# HFT_VHF-UHF-TRX_1V0.net
KiCad netlist of a schematic drawn in EAGLE
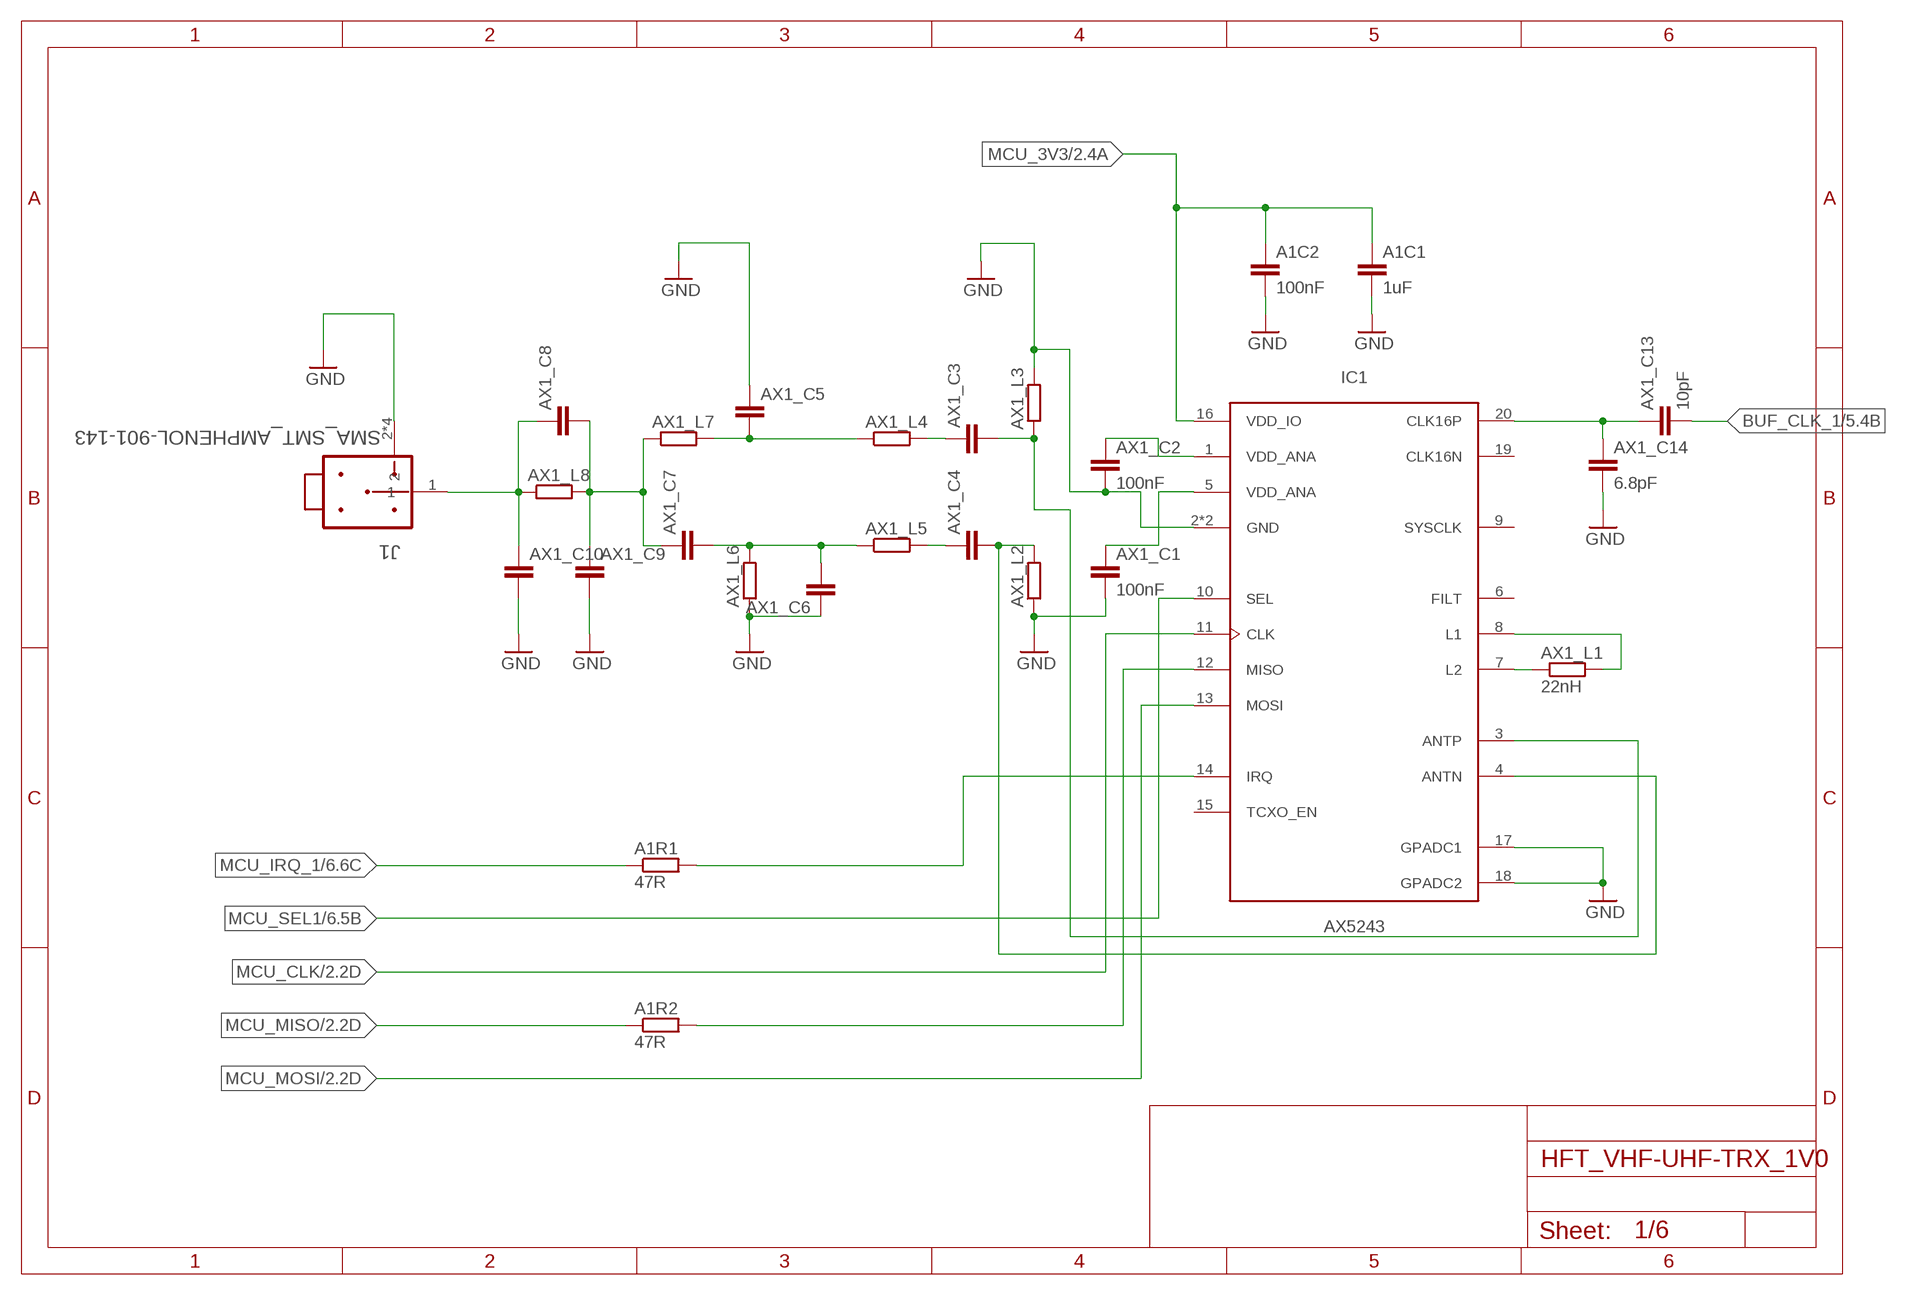
[diagram p0: schematic, sheet 1]
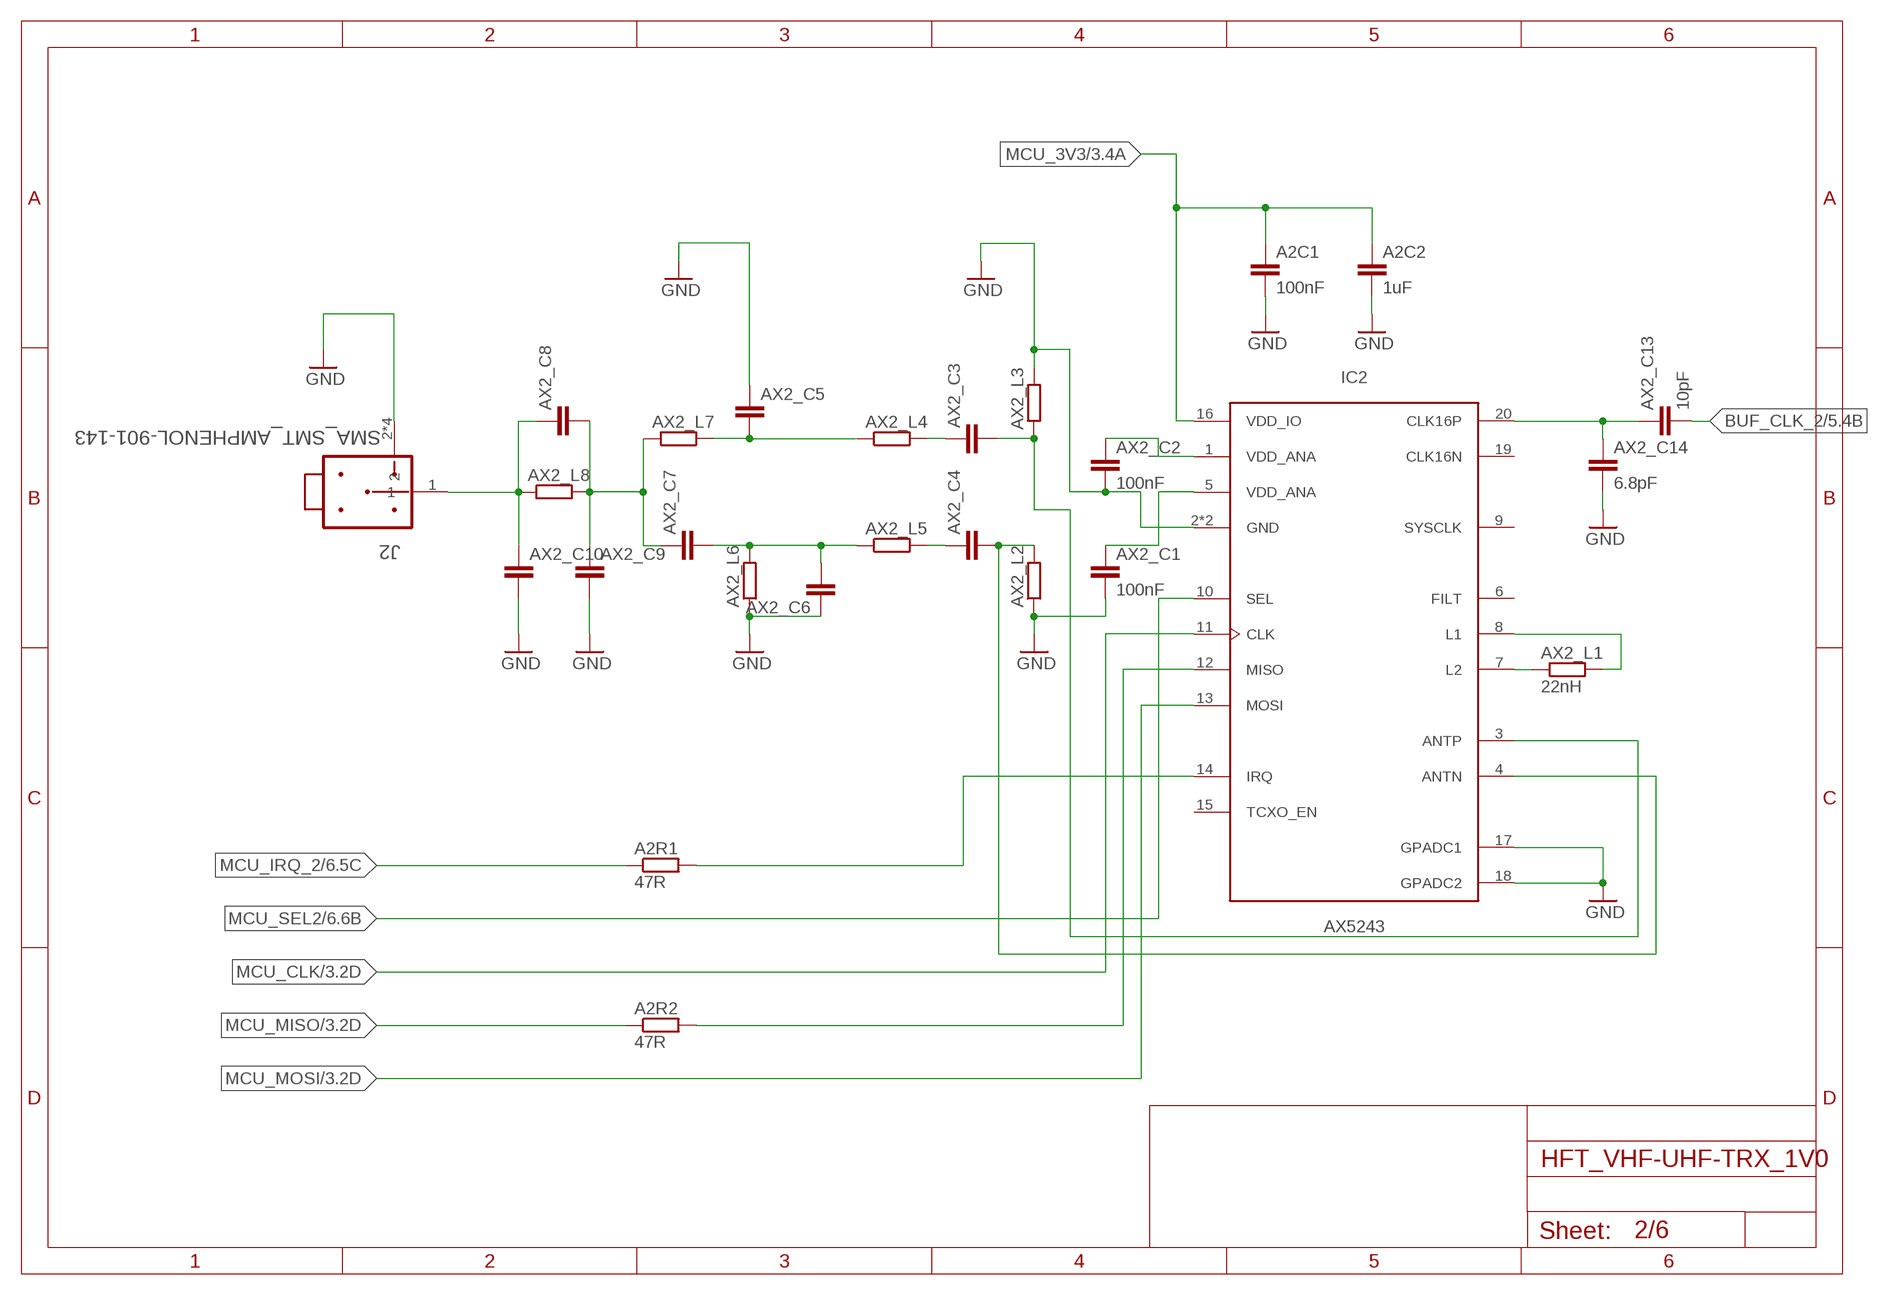
[diagram p1: schematic, sheet 2]
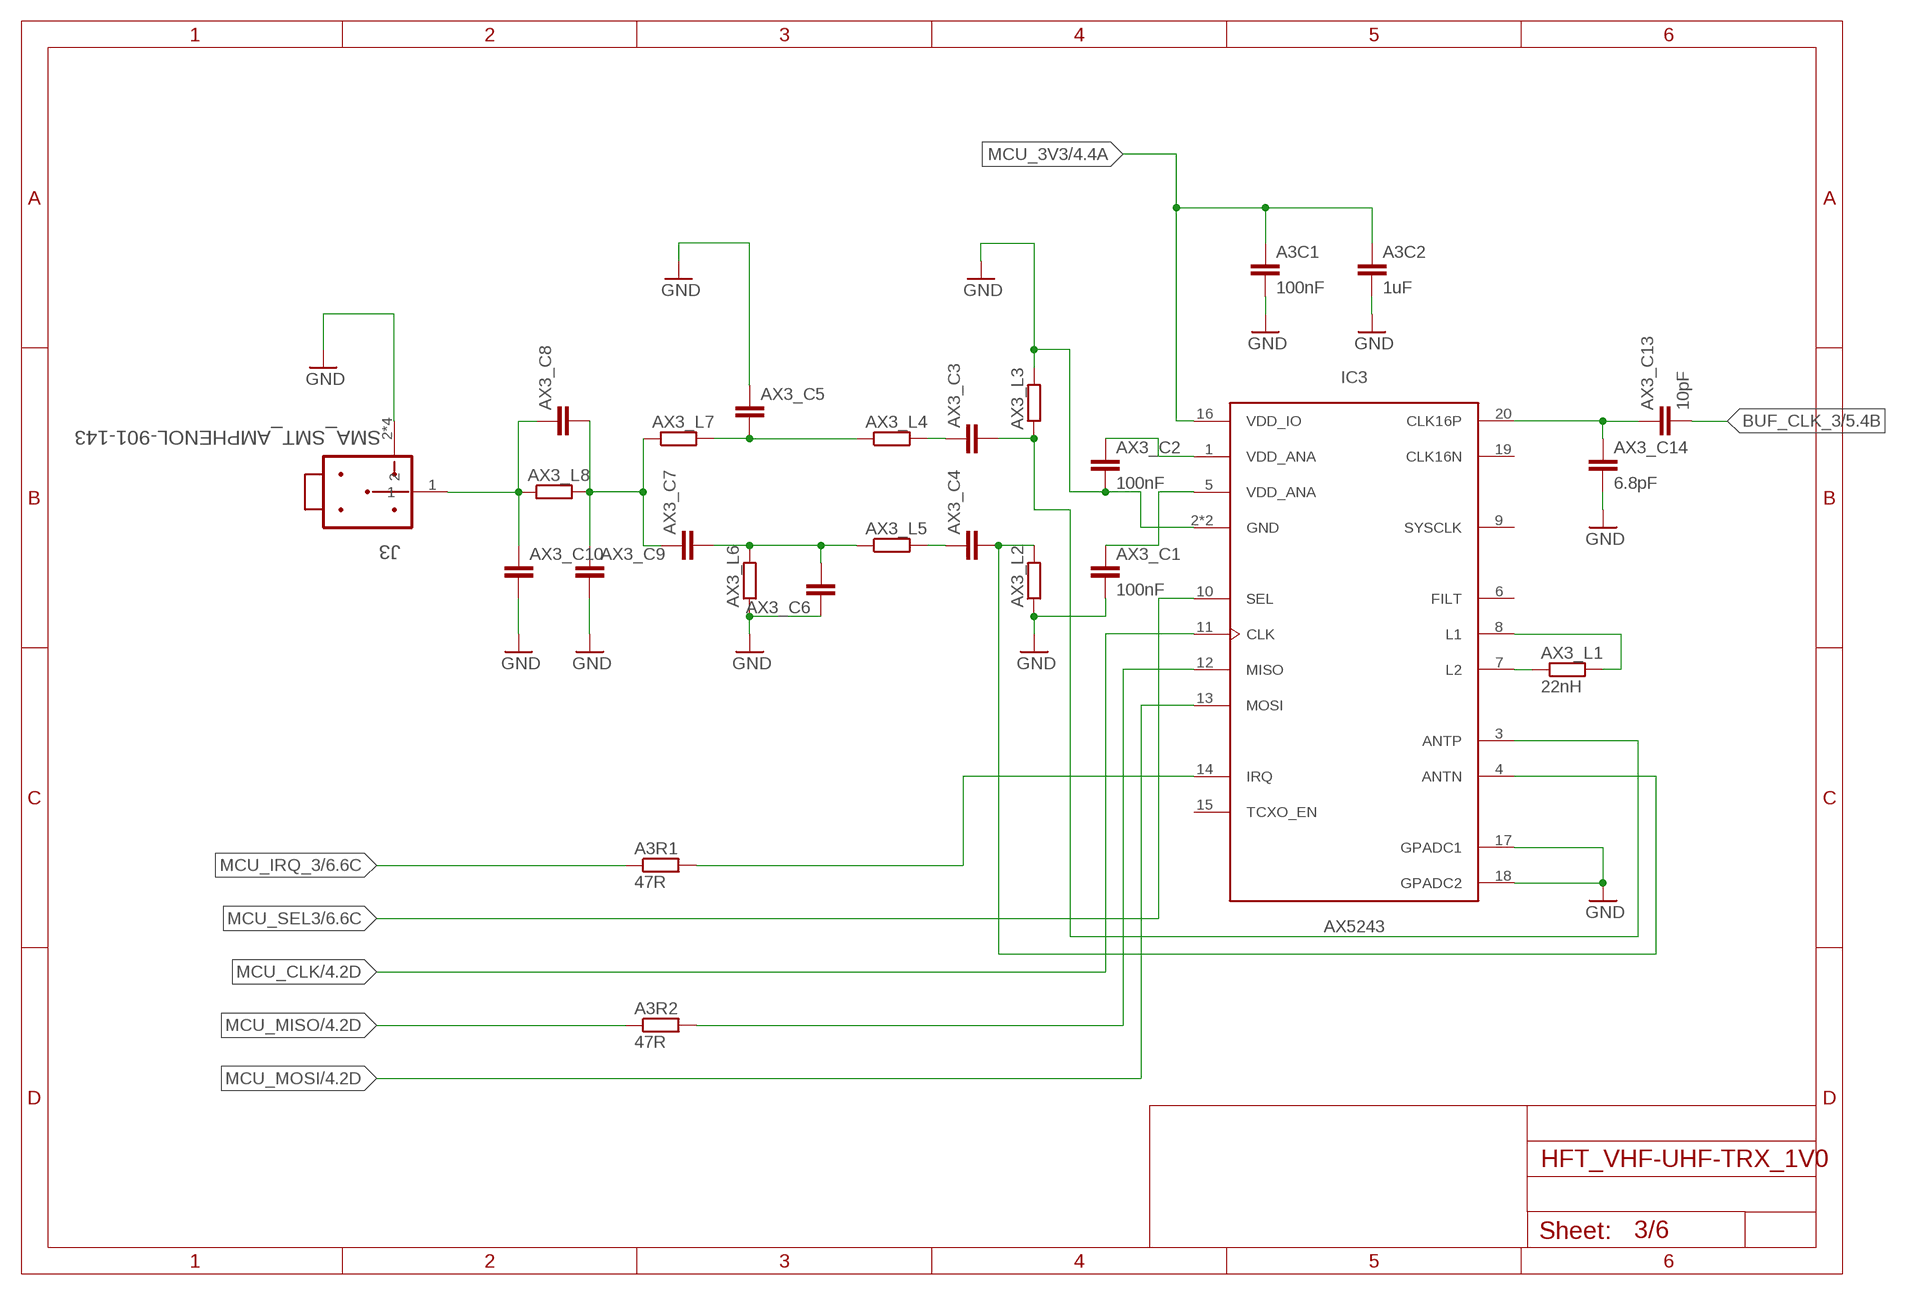
[diagram p2: schematic, sheet 3]
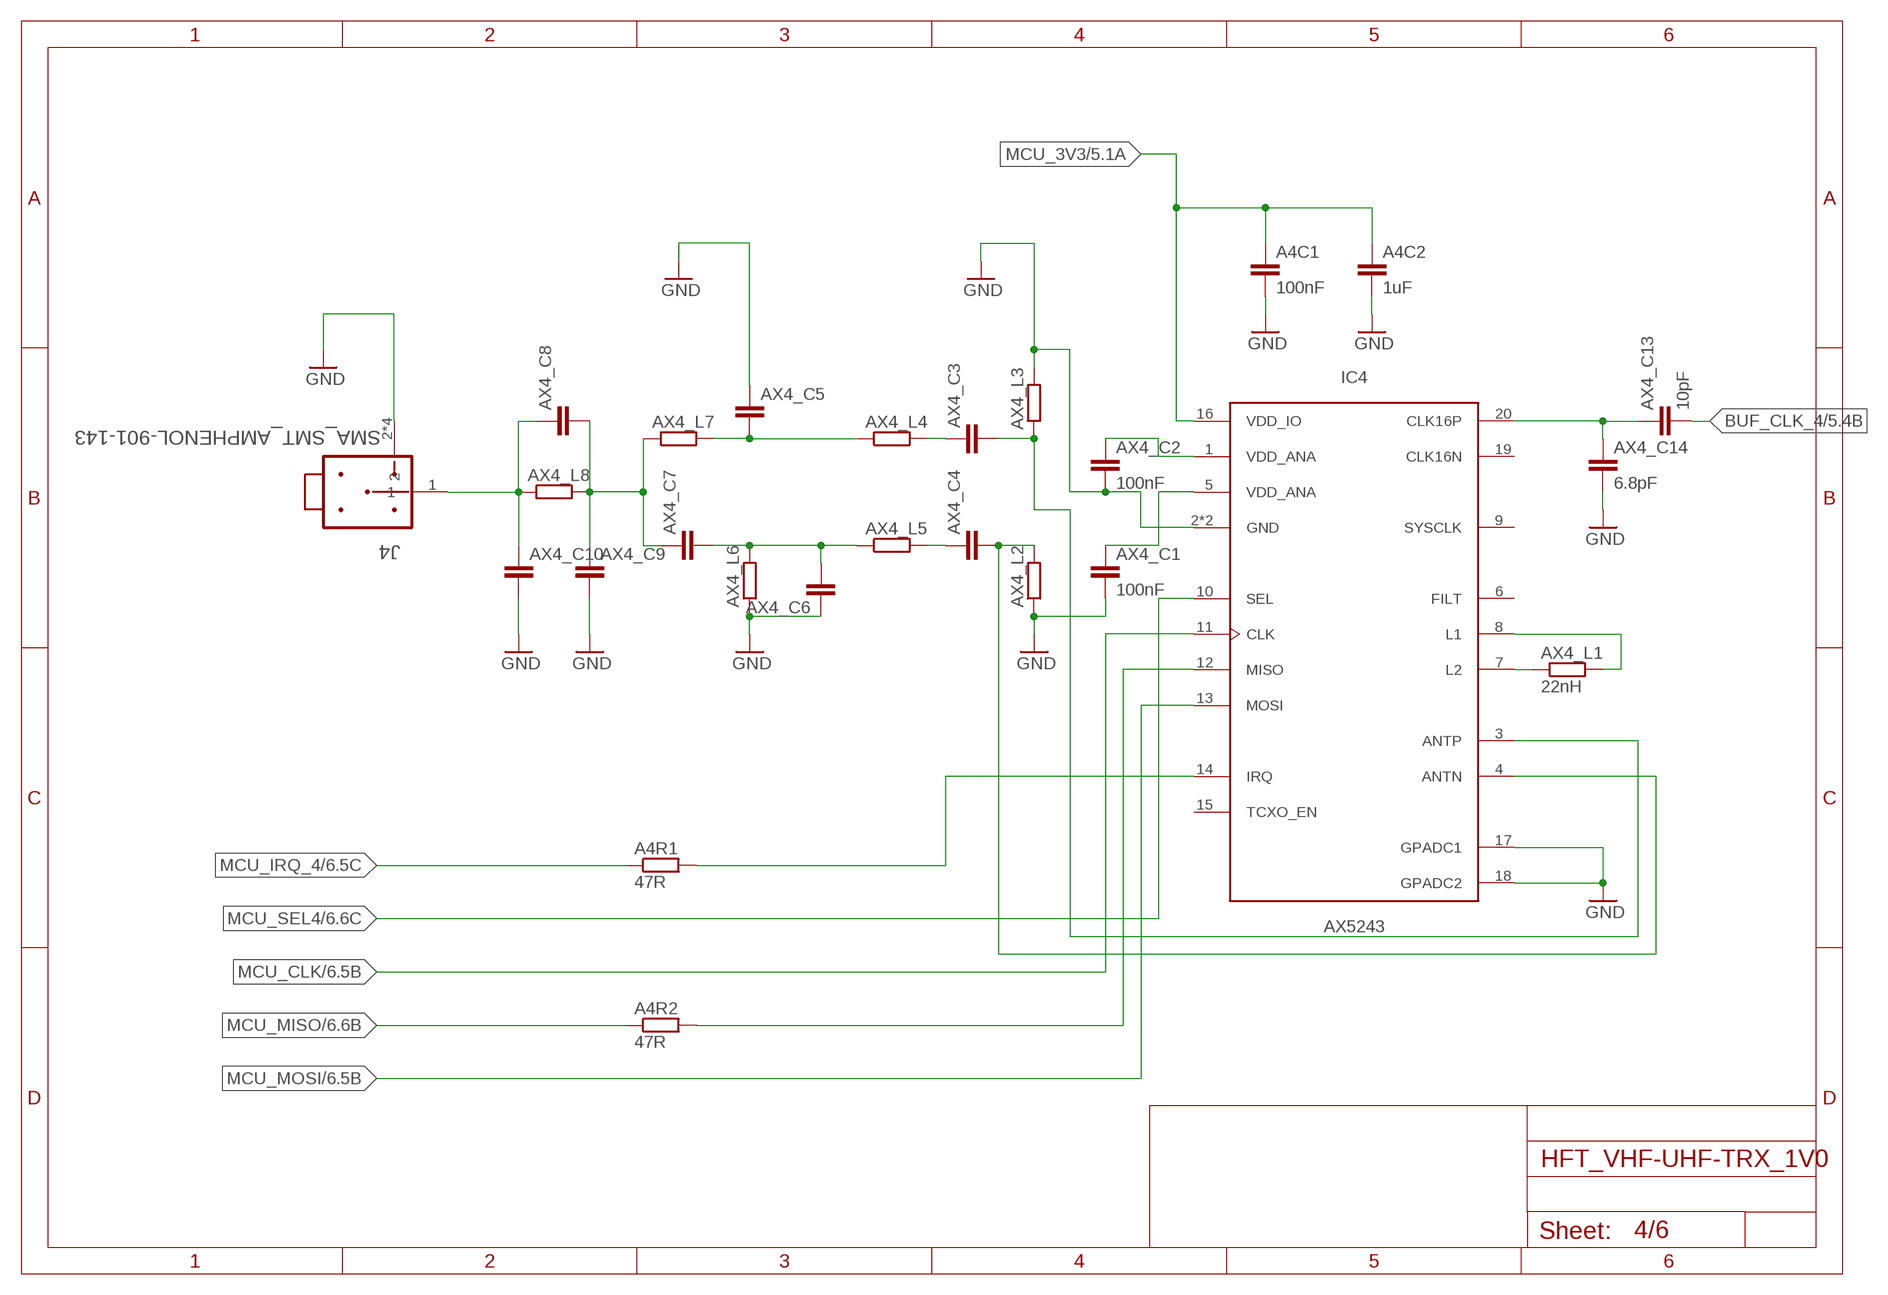
[diagram p3: schematic, sheet 4]
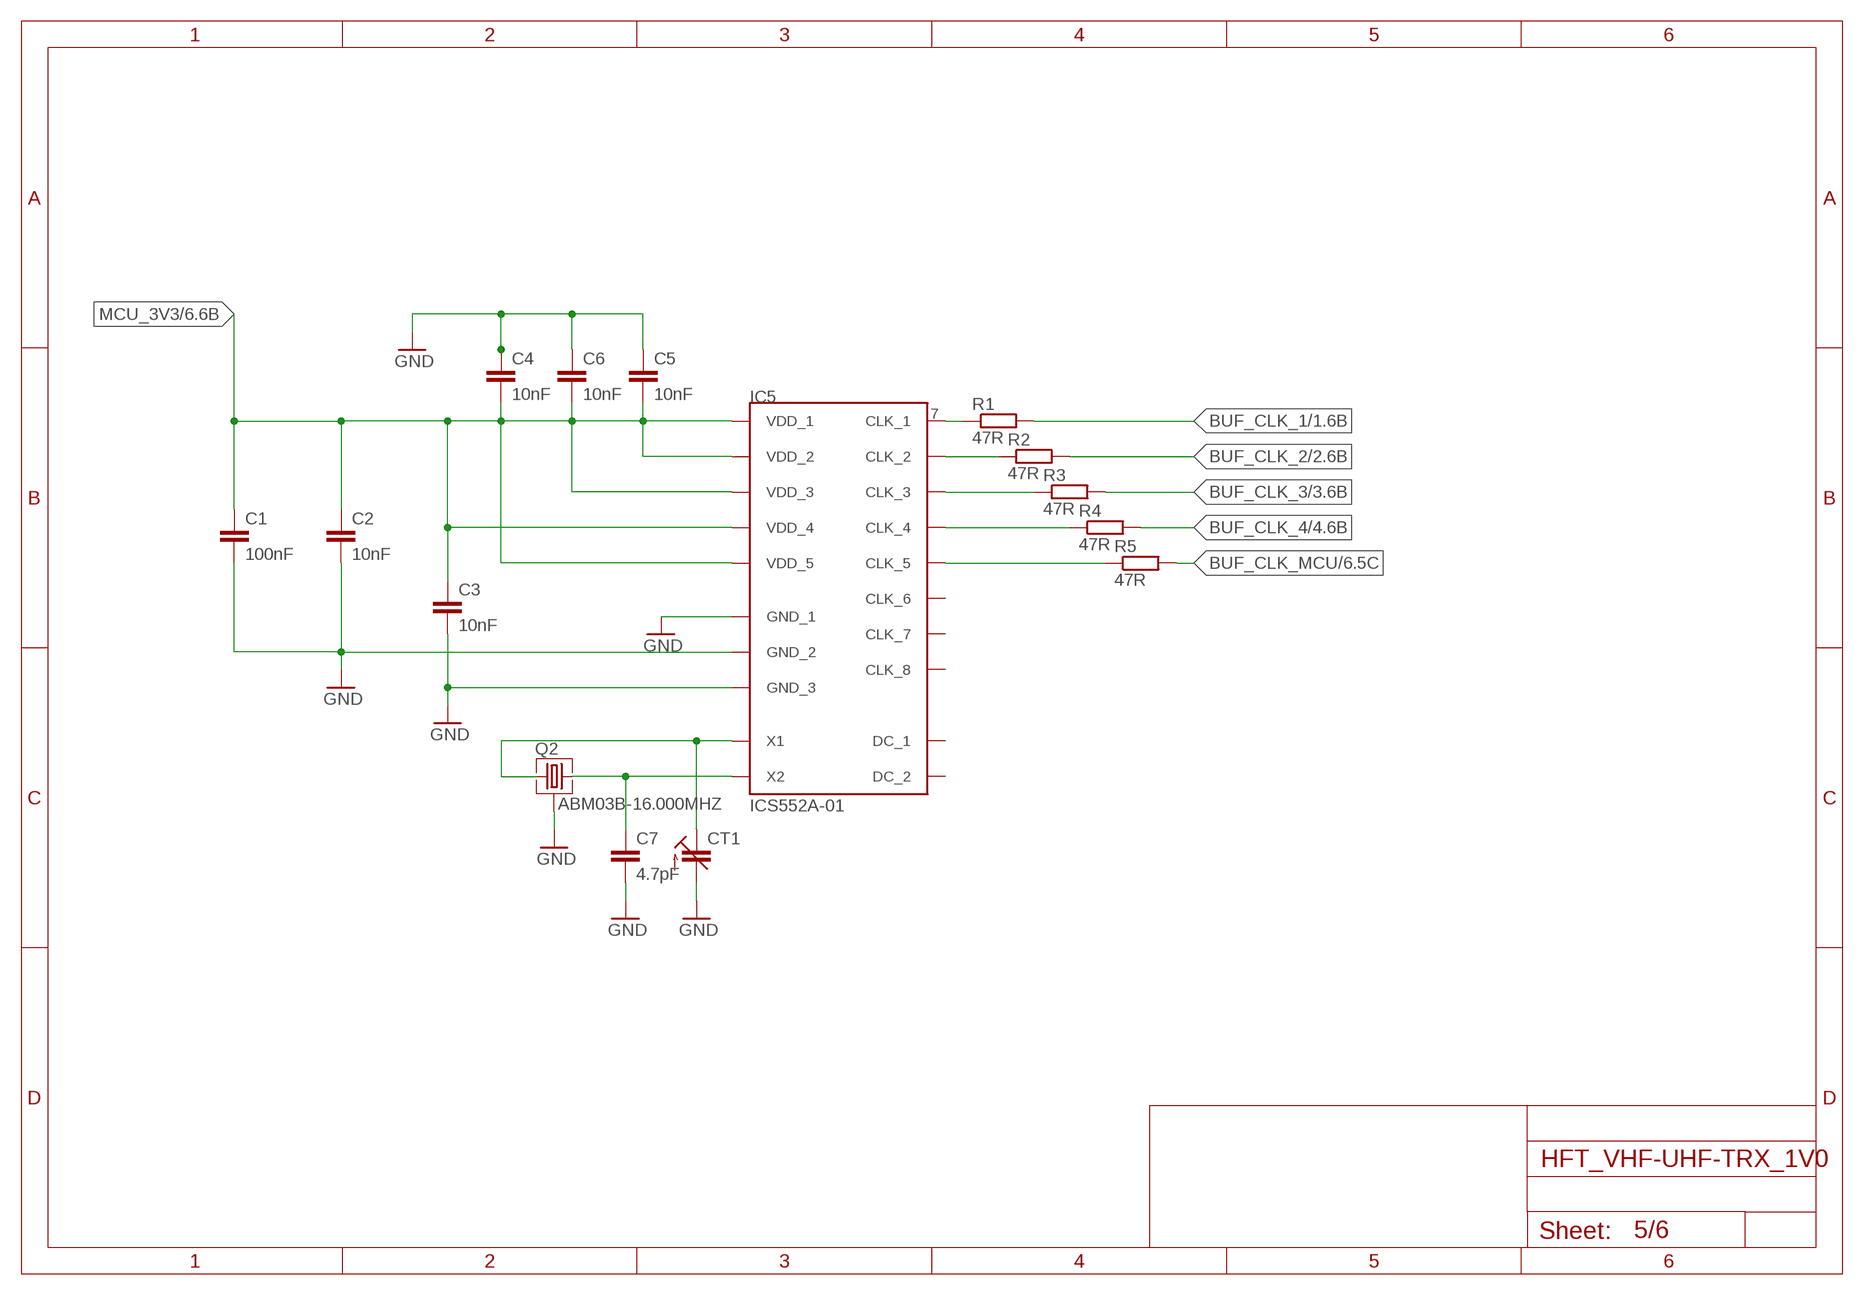
[diagram p4: schematic, sheet 5]
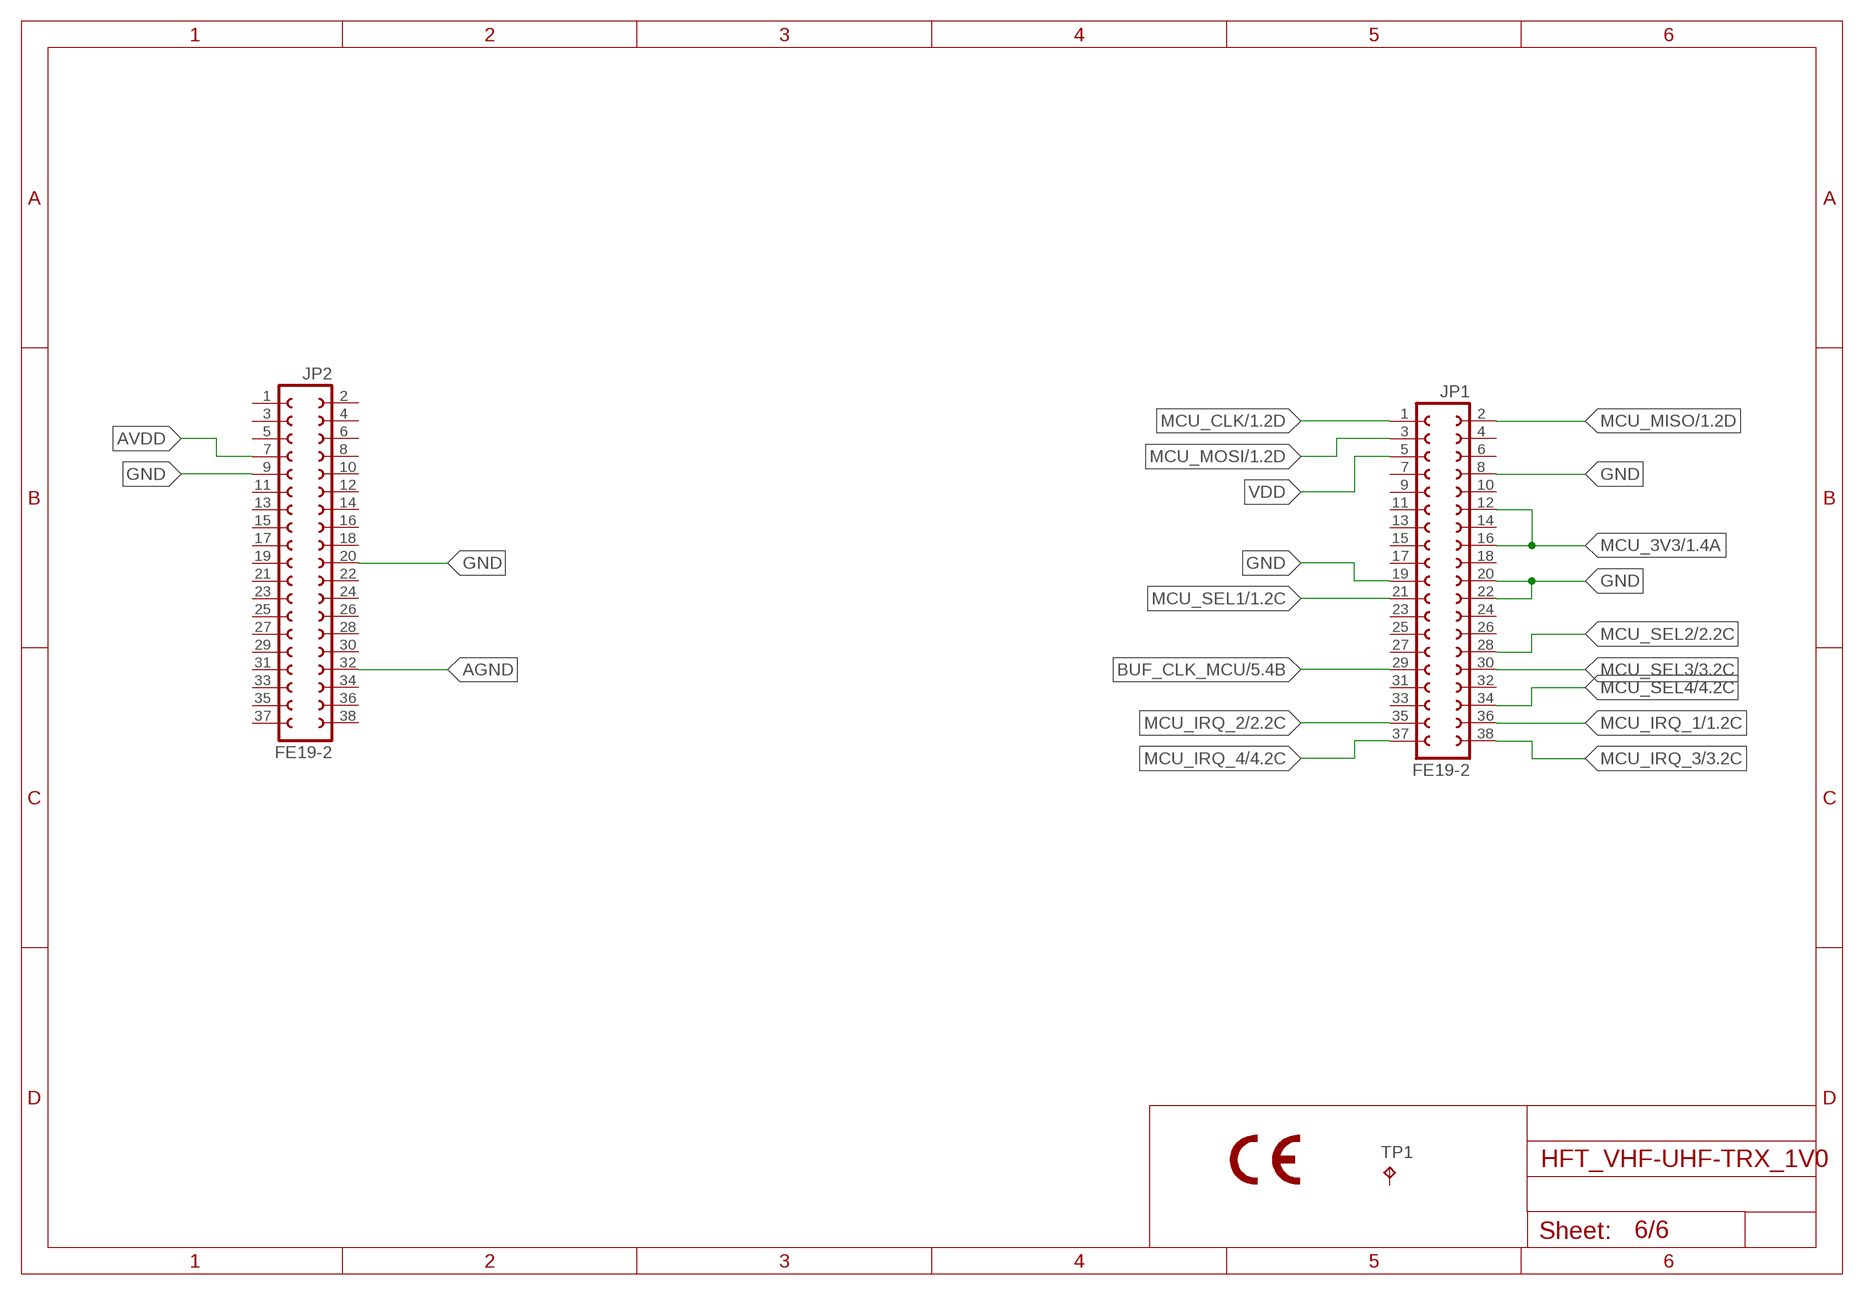
[diagram p5: schematic, sheet 6]

(export (version "E")
  (design (tool "Eeschema 10.0.6"))
  (components
    (comp (ref "JP1")
      (value "FE19-2")
      (footprint "eagle-import:FE19-2")
      (libsource (lib "eagle-import") (part "FE19-2"))
    )
    (comp (ref "JP2")
      (value "FE19-2")
      (footprint "eagle-import:FE19-2")
      (libsource (lib "eagle-import") (part "FE19-2"))
    )
    (comp (ref "TP1")
      (value "TPB1,27")
      (footprint "eagle-import:B1,27")
      (libsource (lib "eagle-import") (part "TPB1,27"))
    )
    (comp (ref "C1")
      (value "100nF")
      (footprint "eagle-import:C0805")
      (libsource (lib "eagle-import") (part "C-EUC0805"))
    )
    (comp (ref "C2")
      (value "10nF")
      (footprint "eagle-import:C0805")
      (libsource (lib "eagle-import") (part "C-EUC0805"))
    )
    (comp (ref "C3")
      (value "10nF")
      (footprint "eagle-import:C0805")
      (libsource (lib "eagle-import") (part "C-EUC0805"))
    )
    (comp (ref "C4")
      (value "10nF")
      (footprint "eagle-import:C0805")
      (libsource (lib "eagle-import") (part "C-EUC0805"))
    )
    (comp (ref "C5")
      (value "10nF")
      (footprint "eagle-import:C0805")
      (libsource (lib "eagle-import") (part "C-EUC0805"))
    )
    (comp (ref "C6")
      (value "10nF")
      (footprint "eagle-import:C0805")
      (libsource (lib "eagle-import") (part "C-EUC0805"))
    )
    (comp (ref "C7")
      (value "4.7pF")
      (footprint "eagle-import:C0805")
      (libsource (lib "eagle-import") (part "C-EUC0805"))
    )
    (comp (ref "CT1")
      (value "C-TRIMM3MM2_2MM5")
      (footprint "eagle-import:3MM2_X_2MM5")
      (libsource (lib "eagle-import") (part "C-TRIMM3MM2_2MM5"))
    )
    (comp (ref "IC5")
      (value "ICS552A-01")
      (footprint "eagle-import:SSOP20")
      (libsource (lib "eagle-import") (part "ICS552A-01"))
    )
    (comp (ref "Q2")
      (value "ABM03B-16.000MHZ")
      (footprint "eagle-import:ABM03B")
      (libsource (lib "eagle-import") (part "ABM03B-16.000MHZ"))
    )
    (comp (ref "R1")
      (value "47R")
      (footprint "eagle-import:R0805")
      (libsource (lib "eagle-import") (part "R-EU_R0805"))
    )
    (comp (ref "R2")
      (value "47R")
      (footprint "eagle-import:R0805")
      (libsource (lib "eagle-import") (part "R-EU_R0805"))
    )
    (comp (ref "R3")
      (value "47R")
      (footprint "eagle-import:R0805")
      (libsource (lib "eagle-import") (part "R-EU_R0805"))
    )
    (comp (ref "R4")
      (value "47R")
      (footprint "eagle-import:R0805")
      (libsource (lib "eagle-import") (part "R-EU_R0805"))
    )
    (comp (ref "R5")
      (value "47R")
      (footprint "eagle-import:R0805")
      (libsource (lib "eagle-import") (part "R-EU_R0805"))
    )
    (comp (ref "A3C1")
      (value "100nF")
      (footprint "eagle-import:C0805")
      (libsource (lib "eagle-import") (part "C-EUC0805"))
    )
    (comp (ref "A3C2")
      (value "1uF")
      (footprint "eagle-import:C0805")
      (libsource (lib "eagle-import") (part "C-EUC0805"))
    )
    (comp (ref "A3R1")
      (value "47R")
      (footprint "eagle-import:R0805")
      (libsource (lib "eagle-import") (part "R-EU_R0805"))
    )
    (comp (ref "A3R2")
      (value "47R")
      (footprint "eagle-import:R0805")
      (libsource (lib "eagle-import") (part "R-EU_R0805"))
    )
    (comp (ref "AX3_C1")
      (value "100nF")
      (footprint "eagle-import:C0805")
      (libsource (lib "eagle-import") (part "C-EUC0805"))
    )
    (comp (ref "AX3_C2")
      (value "100nF")
      (footprint "eagle-import:C0805")
      (libsource (lib "eagle-import") (part "C-EUC0805"))
    )
    (comp (ref "AX3_C3")
      (value "C-EUC0805")
      (footprint "eagle-import:C0805")
      (libsource (lib "eagle-import") (part "C-EUC0805"))
    )
    (comp (ref "AX3_C4")
      (value "C-EUC0805")
      (footprint "eagle-import:C0805")
      (libsource (lib "eagle-import") (part "C-EUC0805"))
    )
    (comp (ref "AX3_C5")
      (value "C-EUC0805")
      (footprint "eagle-import:C0805")
      (libsource (lib "eagle-import") (part "C-EUC0805"))
    )
    (comp (ref "AX3_C6")
      (value "C-EUC0805")
      (footprint "eagle-import:C0805")
      (libsource (lib "eagle-import") (part "C-EUC0805"))
    )
    (comp (ref "AX3_C7")
      (value "C-EUC0805")
      (footprint "eagle-import:C0805")
      (libsource (lib "eagle-import") (part "C-EUC0805"))
    )
    (comp (ref "AX3_C8")
      (value "C-EUC0805")
      (footprint "eagle-import:C0805")
      (libsource (lib "eagle-import") (part "C-EUC0805"))
    )
    (comp (ref "AX3_C9")
      (value "C-EUC0805")
      (footprint "eagle-import:C0805")
      (libsource (lib "eagle-import") (part "C-EUC0805"))
    )
    (comp (ref "AX3_C10")
      (value "C-EUC0805")
      (footprint "eagle-import:C0805")
      (libsource (lib "eagle-import") (part "C-EUC0805"))
    )
    (comp (ref "AX3_C13")
      (value "10pF")
      (footprint "eagle-import:C0805")
      (libsource (lib "eagle-import") (part "C-EUC0805"))
    )
    (comp (ref "AX3_C14")
      (value "6.8pF")
      (footprint "eagle-import:C0805")
      (libsource (lib "eagle-import") (part "C-EUC0805"))
    )
    (comp (ref "AX3_L1")
      (value "22nH")
      (footprint "eagle-import:R0805")
      (libsource (lib "eagle-import") (part "R-EU_R0805"))
    )
    (comp (ref "AX3_L2")
      (value "R-EU_R0805")
      (footprint "eagle-import:R0805")
      (libsource (lib "eagle-import") (part "R-EU_R0805"))
    )
    (comp (ref "AX3_L3")
      (value "R-EU_R0805")
      (footprint "eagle-import:R0805")
      (libsource (lib "eagle-import") (part "R-EU_R0805"))
    )
    (comp (ref "AX3_L4")
      (value "R-EU_R0805")
      (footprint "eagle-import:R0805")
      (libsource (lib "eagle-import") (part "R-EU_R0805"))
    )
    (comp (ref "AX3_L5")
      (value "R-EU_R0805")
      (footprint "eagle-import:R0805")
      (libsource (lib "eagle-import") (part "R-EU_R0805"))
    )
    (comp (ref "AX3_L6")
      (value "R-EU_R0805")
      (footprint "eagle-import:R0805")
      (libsource (lib "eagle-import") (part "R-EU_R0805"))
    )
    (comp (ref "AX3_L7")
      (value "R-EU_R0805")
      (footprint "eagle-import:R0805")
      (libsource (lib "eagle-import") (part "R-EU_R0805"))
    )
    (comp (ref "AX3_L8")
      (value "R-EU_R0805")
      (footprint "eagle-import:R0805")
      (libsource (lib "eagle-import") (part "R-EU_R0805"))
    )
    (comp (ref "IC3")
      (value "AX5243")
      (footprint "eagle-import:QFN20-4X4-0P5-PAD")
      (libsource (lib "eagle-import") (part "AX5243"))
    )
    (comp (ref "J3")
      (value "SMA_SMT_AMPHENOL-901-143")
      (footprint "eagle-import:SMA_SMT_AMPHENOL_901-143")
      (fields (field (name "MPN") "901-143"))
      (libsource (lib "eagle-import") (part "SMA_SMT_AMPHENOL-901-143"))
    )
    (comp (ref "A2C1")
      (value "100nF")
      (footprint "eagle-import:C0805")
      (libsource (lib "eagle-import") (part "C-EUC0805"))
    )
    (comp (ref "A2C2")
      (value "1uF")
      (footprint "eagle-import:C0805")
      (libsource (lib "eagle-import") (part "C-EUC0805"))
    )
    (comp (ref "A2R1")
      (value "47R")
      (footprint "eagle-import:R0805")
      (libsource (lib "eagle-import") (part "R-EU_R0805"))
    )
    (comp (ref "A2R2")
      (value "47R")
      (footprint "eagle-import:R0805")
      (libsource (lib "eagle-import") (part "R-EU_R0805"))
    )
    (comp (ref "AX2_C1")
      (value "100nF")
      (footprint "eagle-import:C0805")
      (libsource (lib "eagle-import") (part "C-EUC0805"))
    )
    (comp (ref "AX2_C2")
      (value "100nF")
      (footprint "eagle-import:C0805")
      (libsource (lib "eagle-import") (part "C-EUC0805"))
    )
    (comp (ref "AX2_C3")
      (value "C-EUC0805")
      (footprint "eagle-import:C0805")
      (libsource (lib "eagle-import") (part "C-EUC0805"))
    )
    (comp (ref "AX2_C4")
      (value "C-EUC0805")
      (footprint "eagle-import:C0805")
      (libsource (lib "eagle-import") (part "C-EUC0805"))
    )
    (comp (ref "AX2_C5")
      (value "C-EUC0805")
      (footprint "eagle-import:C0805")
      (libsource (lib "eagle-import") (part "C-EUC0805"))
    )
    (comp (ref "AX2_C6")
      (value "C-EUC0805")
      (footprint "eagle-import:C0805")
      (libsource (lib "eagle-import") (part "C-EUC0805"))
    )
    (comp (ref "AX2_C7")
      (value "C-EUC0805")
      (footprint "eagle-import:C0805")
      (libsource (lib "eagle-import") (part "C-EUC0805"))
    )
    (comp (ref "AX2_C8")
      (value "C-EUC0805")
      (footprint "eagle-import:C0805")
      (libsource (lib "eagle-import") (part "C-EUC0805"))
    )
    (comp (ref "AX2_C9")
      (value "C-EUC0805")
      (footprint "eagle-import:C0805")
      (libsource (lib "eagle-import") (part "C-EUC0805"))
    )
    (comp (ref "AX2_C10")
      (value "C-EUC0805")
      (footprint "eagle-import:C0805")
      (libsource (lib "eagle-import") (part "C-EUC0805"))
    )
    (comp (ref "AX2_C13")
      (value "10pF")
      (footprint "eagle-import:C0805")
      (libsource (lib "eagle-import") (part "C-EUC0805"))
    )
    (comp (ref "AX2_C14")
      (value "6.8pF")
      (footprint "eagle-import:C0805")
      (libsource (lib "eagle-import") (part "C-EUC0805"))
    )
    (comp (ref "AX2_L1")
      (value "22nH")
      (footprint "eagle-import:R0805")
      (libsource (lib "eagle-import") (part "R-EU_R0805"))
    )
    (comp (ref "AX2_L2")
      (value "R-EU_R0805")
      (footprint "eagle-import:R0805")
      (libsource (lib "eagle-import") (part "R-EU_R0805"))
    )
    (comp (ref "AX2_L3")
      (value "R-EU_R0805")
      (footprint "eagle-import:R0805")
      (libsource (lib "eagle-import") (part "R-EU_R0805"))
    )
    (comp (ref "AX2_L4")
      (value "R-EU_R0805")
      (footprint "eagle-import:R0805")
      (libsource (lib "eagle-import") (part "R-EU_R0805"))
    )
    (comp (ref "AX2_L5")
      (value "R-EU_R0805")
      (footprint "eagle-import:R0805")
      (libsource (lib "eagle-import") (part "R-EU_R0805"))
    )
    (comp (ref "AX2_L6")
      (value "R-EU_R0805")
      (footprint "eagle-import:R0805")
      (libsource (lib "eagle-import") (part "R-EU_R0805"))
    )
    (comp (ref "AX2_L7")
      (value "R-EU_R0805")
      (footprint "eagle-import:R0805")
      (libsource (lib "eagle-import") (part "R-EU_R0805"))
    )
    (comp (ref "AX2_L8")
      (value "R-EU_R0805")
      (footprint "eagle-import:R0805")
      (libsource (lib "eagle-import") (part "R-EU_R0805"))
    )
    (comp (ref "IC2")
      (value "AX5243")
      (footprint "eagle-import:QFN20-4X4-0P5-PAD")
      (libsource (lib "eagle-import") (part "AX5243"))
    )
    (comp (ref "J2")
      (value "SMA_SMT_AMPHENOL-901-143")
      (footprint "eagle-import:SMA_SMT_AMPHENOL_901-143")
      (fields (field (name "MPN") "901-143"))
      (libsource (lib "eagle-import") (part "SMA_SMT_AMPHENOL-901-143"))
    )
    (comp (ref "A4C1")
      (value "100nF")
      (footprint "eagle-import:C0805")
      (libsource (lib "eagle-import") (part "C-EUC0805"))
    )
    (comp (ref "A4C2")
      (value "1uF")
      (footprint "eagle-import:C0805")
      (libsource (lib "eagle-import") (part "C-EUC0805"))
    )
    (comp (ref "A4R1")
      (value "47R")
      (footprint "eagle-import:R0805")
      (libsource (lib "eagle-import") (part "R-EU_R0805"))
    )
    (comp (ref "A4R2")
      (value "47R")
      (footprint "eagle-import:R0805")
      (libsource (lib "eagle-import") (part "R-EU_R0805"))
    )
    (comp (ref "AX4_C1")
      (value "100nF")
      (footprint "eagle-import:C0805")
      (libsource (lib "eagle-import") (part "C-EUC0805"))
    )
    (comp (ref "AX4_C2")
      (value "100nF")
      (footprint "eagle-import:C0805")
      (libsource (lib "eagle-import") (part "C-EUC0805"))
    )
    (comp (ref "AX4_C3")
      (value "C-EUC0805")
      (footprint "eagle-import:C0805")
      (libsource (lib "eagle-import") (part "C-EUC0805"))
    )
    (comp (ref "AX4_C4")
      (value "C-EUC0805")
      (footprint "eagle-import:C0805")
      (libsource (lib "eagle-import") (part "C-EUC0805"))
    )
    (comp (ref "AX4_C5")
      (value "C-EUC0805")
      (footprint "eagle-import:C0805")
      (libsource (lib "eagle-import") (part "C-EUC0805"))
    )
    (comp (ref "AX4_C6")
      (value "C-EUC0805")
      (footprint "eagle-import:C0805")
      (libsource (lib "eagle-import") (part "C-EUC0805"))
    )
    (comp (ref "AX4_C7")
      (value "C-EUC0805")
      (footprint "eagle-import:C0805")
      (libsource (lib "eagle-import") (part "C-EUC0805"))
    )
    (comp (ref "AX4_C8")
      (value "C-EUC0805")
      (footprint "eagle-import:C0805")
      (libsource (lib "eagle-import") (part "C-EUC0805"))
    )
    (comp (ref "AX4_C9")
      (value "C-EUC0805")
      (footprint "eagle-import:C0805")
      (libsource (lib "eagle-import") (part "C-EUC0805"))
    )
    (comp (ref "AX4_C10")
      (value "C-EUC0805")
      (footprint "eagle-import:C0805")
      (libsource (lib "eagle-import") (part "C-EUC0805"))
    )
    (comp (ref "AX4_C13")
      (value "10pF")
      (footprint "eagle-import:C0805")
      (libsource (lib "eagle-import") (part "C-EUC0805"))
    )
    (comp (ref "AX4_C14")
      (value "6.8pF")
      (footprint "eagle-import:C0805")
      (libsource (lib "eagle-import") (part "C-EUC0805"))
    )
    (comp (ref "AX4_L1")
      (value "22nH")
      (footprint "eagle-import:R0805")
      (libsource (lib "eagle-import") (part "R-EU_R0805"))
    )
    (comp (ref "AX4_L2")
      (value "R-EU_R0805")
      (footprint "eagle-import:R0805")
      (libsource (lib "eagle-import") (part "R-EU_R0805"))
    )
    (comp (ref "AX4_L3")
      (value "R-EU_R0805")
      (footprint "eagle-import:R0805")
      (libsource (lib "eagle-import") (part "R-EU_R0805"))
    )
    (comp (ref "AX4_L4")
      (value "R-EU_R0805")
      (footprint "eagle-import:R0805")
      (libsource (lib "eagle-import") (part "R-EU_R0805"))
    )
    (comp (ref "AX4_L5")
      (value "R-EU_R0805")
      (footprint "eagle-import:R0805")
      (libsource (lib "eagle-import") (part "R-EU_R0805"))
    )
    (comp (ref "AX4_L6")
      (value "R-EU_R0805")
      (footprint "eagle-import:R0805")
      (libsource (lib "eagle-import") (part "R-EU_R0805"))
    )
    (comp (ref "AX4_L7")
      (value "R-EU_R0805")
      (footprint "eagle-import:R0805")
      (libsource (lib "eagle-import") (part "R-EU_R0805"))
    )
    (comp (ref "AX4_L8")
      (value "R-EU_R0805")
      (footprint "eagle-import:R0805")
      (libsource (lib "eagle-import") (part "R-EU_R0805"))
    )
    (comp (ref "IC4")
      (value "AX5243")
      (footprint "eagle-import:QFN20-4X4-0P5-PAD")
      (libsource (lib "eagle-import") (part "AX5243"))
    )
    (comp (ref "J4")
      (value "SMA_SMT_AMPHENOL-901-143")
      (footprint "eagle-import:SMA_SMT_AMPHENOL_901-143")
      (fields (field (name "MPN") "901-143"))
      (libsource (lib "eagle-import") (part "SMA_SMT_AMPHENOL-901-143"))
    )
    (comp (ref "A1C1")
      (value "1uF")
      (footprint "eagle-import:C0805")
      (libsource (lib "eagle-import") (part "C-EUC0805"))
    )
    (comp (ref "A1C2")
      (value "100nF")
      (footprint "eagle-import:C0805")
      (libsource (lib "eagle-import") (part "C-EUC0805"))
    )
    (comp (ref "A1R1")
      (value "47R")
      (footprint "eagle-import:R0805")
      (libsource (lib "eagle-import") (part "R-EU_R0805"))
    )
    (comp (ref "A1R2")
      (value "47R")
      (footprint "eagle-import:R0805")
      (libsource (lib "eagle-import") (part "R-EU_R0805"))
    )
    (comp (ref "AX1_C1")
      (value "100nF")
      (footprint "eagle-import:C0805")
      (libsource (lib "eagle-import") (part "C-EUC0805"))
    )
    (comp (ref "AX1_C2")
      (value "100nF")
      (footprint "eagle-import:C0805")
      (libsource (lib "eagle-import") (part "C-EUC0805"))
    )
    (comp (ref "AX1_C3")
      (value "C-EUC0805")
      (footprint "eagle-import:C0805")
      (libsource (lib "eagle-import") (part "C-EUC0805"))
    )
    (comp (ref "AX1_C4")
      (value "C-EUC0805")
      (footprint "eagle-import:C0805")
      (libsource (lib "eagle-import") (part "C-EUC0805"))
    )
    (comp (ref "AX1_C5")
      (value "C-EUC0805")
      (footprint "eagle-import:C0805")
      (libsource (lib "eagle-import") (part "C-EUC0805"))
    )
    (comp (ref "AX1_C6")
      (value "C-EUC0805")
      (footprint "eagle-import:C0805")
      (libsource (lib "eagle-import") (part "C-EUC0805"))
    )
    (comp (ref "AX1_C7")
      (value "C-EUC0805")
      (footprint "eagle-import:C0805")
      (libsource (lib "eagle-import") (part "C-EUC0805"))
    )
    (comp (ref "AX1_C8")
      (value "C-EUC0805")
      (footprint "eagle-import:C0805")
      (libsource (lib "eagle-import") (part "C-EUC0805"))
    )
    (comp (ref "AX1_C9")
      (value "C-EUC0805")
      (footprint "eagle-import:C0805")
      (libsource (lib "eagle-import") (part "C-EUC0805"))
    )
    (comp (ref "AX1_C10")
      (value "C-EUC0805")
      (footprint "eagle-import:C0805")
      (libsource (lib "eagle-import") (part "C-EUC0805"))
    )
    (comp (ref "AX1_C13")
      (value "10pF")
      (footprint "eagle-import:C0805")
      (libsource (lib "eagle-import") (part "C-EUC0805"))
    )
    (comp (ref "AX1_C14")
      (value "6.8pF")
      (footprint "eagle-import:C0805")
      (libsource (lib "eagle-import") (part "C-EUC0805"))
    )
    (comp (ref "AX1_L1")
      (value "22nH")
      (footprint "eagle-import:R0805")
      (libsource (lib "eagle-import") (part "R-EU_R0805"))
    )
    (comp (ref "AX1_L2")
      (value "R-EU_R0805")
      (footprint "eagle-import:R0805")
      (libsource (lib "eagle-import") (part "R-EU_R0805"))
    )
    (comp (ref "AX1_L3")
      (value "R-EU_R0805")
      (footprint "eagle-import:R0805")
      (libsource (lib "eagle-import") (part "R-EU_R0805"))
    )
    (comp (ref "AX1_L4")
      (value "R-EU_R0805")
      (footprint "eagle-import:R0805")
      (libsource (lib "eagle-import") (part "R-EU_R0805"))
    )
    (comp (ref "AX1_L5")
      (value "R-EU_R0805")
      (footprint "eagle-import:R0805")
      (libsource (lib "eagle-import") (part "R-EU_R0805"))
    )
    (comp (ref "AX1_L6")
      (value "R-EU_R0805")
      (footprint "eagle-import:R0805")
      (libsource (lib "eagle-import") (part "R-EU_R0805"))
    )
    (comp (ref "AX1_L7")
      (value "R-EU_R0805")
      (footprint "eagle-import:R0805")
      (libsource (lib "eagle-import") (part "R-EU_R0805"))
    )
    (comp (ref "AX1_L8")
      (value "R-EU_R0805")
      (footprint "eagle-import:R0805")
      (libsource (lib "eagle-import") (part "R-EU_R0805"))
    )
    (comp (ref "IC1")
      (value "AX5243")
      (footprint "eagle-import:QFN20-4X4-0P5-PAD")
      (libsource (lib "eagle-import") (part "AX5243"))
    )
    (comp (ref "J1")
      (value "SMA_SMT_AMPHENOL-901-143")
      (footprint "eagle-import:SMA_SMT_AMPHENOL_901-143")
      (fields (field (name "MPN") "901-143"))
      (libsource (lib "eagle-import") (part "SMA_SMT_AMPHENOL-901-143"))
    )
  )
  (nets
    (net (code "1") (name "AGND") (class "Default")
      (node (ref "JP2") (pin "32") (pinfunction "32_32") (pintype "passive"))
    )
    (net (code "2") (name "AVDD") (class "Default")
      (node (ref "JP2") (pin "7") (pinfunction "7_7") (pintype "passive"))
    )
    (net (code "3") (name "BUF_CLK_1") (class "Default")
      (node (ref "AX1_C13") (pin "2") (pinfunction "2_2") (pintype "passive"))
      (node (ref "R1") (pin "2") (pinfunction "2_2") (pintype "passive"))
    )
    (net (code "4") (name "BUF_CLK_2") (class "Default")
      (node (ref "AX2_C13") (pin "2") (pinfunction "2_2") (pintype "passive"))
      (node (ref "R2") (pin "2") (pinfunction "2_2") (pintype "passive"))
    )
    (net (code "5") (name "BUF_CLK_3") (class "Default")
      (node (ref "AX3_C13") (pin "2") (pinfunction "2_2") (pintype "passive"))
      (node (ref "R3") (pin "2") (pinfunction "2_2") (pintype "passive"))
    )
    (net (code "6") (name "BUF_CLK_4") (class "Default")
      (node (ref "AX4_C13") (pin "2") (pinfunction "2_2") (pintype "passive"))
      (node (ref "R4") (pin "2") (pinfunction "2_2") (pintype "passive"))
    )
    (net (code "7") (name "BUF_CLK_MCU") (class "Default")
      (node (ref "JP1") (pin "29") (pinfunction "29_29") (pintype "passive"))
      (node (ref "R5") (pin "2") (pinfunction "2_2") (pintype "passive"))
    )
    (net (code "8") (name "GND") (class "Default")
      (node (ref "A1C1") (pin "2") (pinfunction "2_2") (pintype "passive"))
      (node (ref "A1C2") (pin "2") (pinfunction "2_2") (pintype "passive"))
      (node (ref "A2C1") (pin "2") (pinfunction "2_2") (pintype "passive"))
      (node (ref "A2C2") (pin "2") (pinfunction "2_2") (pintype "passive"))
      (node (ref "A3C1") (pin "2") (pinfunction "2_2") (pintype "passive"))
      (node (ref "A3C2") (pin "2") (pinfunction "2_2") (pintype "passive"))
      (node (ref "A4C1") (pin "2") (pinfunction "2_2") (pintype "passive"))
      (node (ref "A4C2") (pin "2") (pinfunction "2_2") (pintype "passive"))
      (node (ref "AX1_C1") (pin "2") (pinfunction "2_2") (pintype "passive"))
      (node (ref "AX1_C10") (pin "2") (pinfunction "2_2") (pintype "passive"))
      (node (ref "AX1_C14") (pin "2") (pinfunction "2_2") (pintype "passive"))
      (node (ref "AX1_C2") (pin "2") (pinfunction "2_2") (pintype "passive"))
      (node (ref "AX1_C5") (pin "1") (pinfunction "1_1") (pintype "passive"))
      (node (ref "AX1_C6") (pin "1") (pinfunction "1_1") (pintype "passive"))
      (node (ref "AX1_C9") (pin "2") (pinfunction "2_2") (pintype "passive"))
      (node (ref "AX1_L2") (pin "1") (pinfunction "1_1") (pintype "passive"))
      (node (ref "AX1_L3") (pin "2") (pinfunction "2_2") (pintype "passive"))
      (node (ref "AX1_L6") (pin "1") (pinfunction "1_1") (pintype "passive"))
      (node (ref "AX2_C1") (pin "2") (pinfunction "2_2") (pintype "passive"))
      (node (ref "AX2_C10") (pin "2") (pinfunction "2_2") (pintype "passive"))
      (node (ref "AX2_C14") (pin "2") (pinfunction "2_2") (pintype "passive"))
      (node (ref "AX2_C2") (pin "2") (pinfunction "2_2") (pintype "passive"))
      (node (ref "AX2_C5") (pin "1") (pinfunction "1_1") (pintype "passive"))
      (node (ref "AX2_C6") (pin "1") (pinfunction "1_1") (pintype "passive"))
      (node (ref "AX2_C9") (pin "2") (pinfunction "2_2") (pintype "passive"))
      (node (ref "AX2_L2") (pin "1") (pinfunction "1_1") (pintype "passive"))
      (node (ref "AX2_L3") (pin "2") (pinfunction "2_2") (pintype "passive"))
      (node (ref "AX2_L6") (pin "1") (pinfunction "1_1") (pintype "passive"))
      (node (ref "AX3_C1") (pin "2") (pinfunction "2_2") (pintype "passive"))
      (node (ref "AX3_C10") (pin "2") (pinfunction "2_2") (pintype "passive"))
      (node (ref "AX3_C14") (pin "2") (pinfunction "2_2") (pintype "passive"))
      (node (ref "AX3_C2") (pin "2") (pinfunction "2_2") (pintype "passive"))
      (node (ref "AX3_C5") (pin "1") (pinfunction "1_1") (pintype "passive"))
      (node (ref "AX3_C6") (pin "1") (pinfunction "1_1") (pintype "passive"))
      (node (ref "AX3_C9") (pin "2") (pinfunction "2_2") (pintype "passive"))
      (node (ref "AX3_L2") (pin "1") (pinfunction "1_1") (pintype "passive"))
      (node (ref "AX3_L3") (pin "2") (pinfunction "2_2") (pintype "passive"))
      (node (ref "AX3_L6") (pin "1") (pinfunction "1_1") (pintype "passive"))
      (node (ref "AX4_C1") (pin "2") (pinfunction "2_2") (pintype "passive"))
      (node (ref "AX4_C10") (pin "2") (pinfunction "2_2") (pintype "passive"))
      (node (ref "AX4_C14") (pin "2") (pinfunction "2_2") (pintype "passive"))
      (node (ref "AX4_C2") (pin "2") (pinfunction "2_2") (pintype "passive"))
      (node (ref "AX4_C5") (pin "1") (pinfunction "1_1") (pintype "passive"))
      (node (ref "AX4_C6") (pin "1") (pinfunction "1_1") (pintype "passive"))
      (node (ref "AX4_C9") (pin "2") (pinfunction "2_2") (pintype "passive"))
      (node (ref "AX4_L2") (pin "1") (pinfunction "1_1") (pintype "passive"))
      (node (ref "AX4_L3") (pin "2") (pinfunction "2_2") (pintype "passive"))
      (node (ref "AX4_L6") (pin "1") (pinfunction "1_1") (pintype "passive"))
      (node (ref "C1") (pin "2") (pinfunction "2_2") (pintype "passive"))
      (node (ref "C2") (pin "2") (pinfunction "2_2") (pintype "passive"))
      (node (ref "C3") (pin "2") (pinfunction "2_2") (pintype "passive"))
      (node (ref "C4") (pin "1") (pinfunction "1_1") (pintype "passive"))
      (node (ref "C5") (pin "1") (pinfunction "1_1") (pintype "passive"))
      (node (ref "C6") (pin "1") (pinfunction "1_1") (pintype "passive"))
      (node (ref "C7") (pin "2") (pinfunction "2_2") (pintype "passive"))
      (node (ref "CT1") (pin "+") (pinfunction "A_+") (pintype "passive"))
      (node (ref "IC1") (pin "17") (pinfunction "GPADC1_17") (pintype "passive"))
      (node (ref "IC1") (pin "18") (pinfunction "GPADC2_18") (pintype "passive"))
      (node (ref "IC1") (pin "2") (pinfunction "GND_2") (pintype "power_in"))
      (node (ref "IC1") (pin "21") (pinfunction "GND_21") (pintype "power_in"))
      (node (ref "IC2") (pin "17") (pinfunction "GPADC1_17") (pintype "passive"))
      (node (ref "IC2") (pin "18") (pinfunction "GPADC2_18") (pintype "passive"))
      (node (ref "IC2") (pin "2") (pinfunction "GND_2") (pintype "power_in"))
      (node (ref "IC2") (pin "21") (pinfunction "GND_21") (pintype "power_in"))
      (node (ref "IC3") (pin "17") (pinfunction "GPADC1_17") (pintype "passive"))
      (node (ref "IC3") (pin "18") (pinfunction "GPADC2_18") (pintype "passive"))
      (node (ref "IC3") (pin "2") (pinfunction "GND_2") (pintype "power_in"))
      (node (ref "IC3") (pin "21") (pinfunction "GND_21") (pintype "power_in"))
      (node (ref "IC4") (pin "17") (pinfunction "GPADC1_17") (pintype "passive"))
      (node (ref "IC4") (pin "18") (pinfunction "GPADC2_18") (pintype "passive"))
      (node (ref "IC4") (pin "2") (pinfunction "GND_2") (pintype "power_in"))
      (node (ref "IC4") (pin "21") (pinfunction "GND_21") (pintype "power_in"))
      (node (ref "IC5") (pin "14") (pinfunction "GND_3_14") (pintype "passive"))
      (node (ref "IC5") (pin "5") (pinfunction "GND_1_5") (pintype "passive"))
      (node (ref "IC5") (pin "6") (pinfunction "GND_2_6") (pintype "passive"))
      (node (ref "J1") (pin "2") (pinfunction "2_2") (pintype "passive"))
      (node (ref "J1") (pin "3") (pinfunction "2_3") (pintype "passive"))
      (node (ref "J1") (pin "4") (pinfunction "2_4") (pintype "passive"))
      (node (ref "J1") (pin "5") (pinfunction "2_5") (pintype "passive"))
      (node (ref "J2") (pin "2") (pinfunction "2_2") (pintype "passive"))
      (node (ref "J2") (pin "3") (pinfunction "2_3") (pintype "passive"))
      (node (ref "J2") (pin "4") (pinfunction "2_4") (pintype "passive"))
      (node (ref "J2") (pin "5") (pinfunction "2_5") (pintype "passive"))
      (node (ref "J3") (pin "2") (pinfunction "2_2") (pintype "passive"))
      (node (ref "J3") (pin "3") (pinfunction "2_3") (pintype "passive"))
      (node (ref "J3") (pin "4") (pinfunction "2_4") (pintype "passive"))
      (node (ref "J3") (pin "5") (pinfunction "2_5") (pintype "passive"))
      (node (ref "J4") (pin "2") (pinfunction "2_2") (pintype "passive"))
      (node (ref "J4") (pin "3") (pinfunction "2_3") (pintype "passive"))
      (node (ref "J4") (pin "4") (pinfunction "2_4") (pintype "passive"))
      (node (ref "J4") (pin "5") (pinfunction "2_5") (pintype "passive"))
      (node (ref "JP1") (pin "19") (pinfunction "19_19") (pintype "passive"))
      (node (ref "JP1") (pin "20") (pinfunction "20_20") (pintype "passive"))
      (node (ref "JP1") (pin "22") (pinfunction "22_22") (pintype "passive"))
      (node (ref "JP1") (pin "8") (pinfunction "8_8") (pintype "passive"))
      (node (ref "JP2") (pin "20") (pinfunction "20_20") (pintype "passive"))
      (node (ref "JP2") (pin "9") (pinfunction "9_9") (pintype "passive"))
      (node (ref "Q2") (pin "2") (pinfunction "3_2") (pintype "passive"))
      (node (ref "Q2") (pin "4") (pinfunction "3_4") (pintype "passive"))
    )
    (net (code "9") (name "MCU_3V3") (class "Default")
      (node (ref "A1C1") (pin "1") (pinfunction "1_1") (pintype "passive"))
      (node (ref "A1C2") (pin "1") (pinfunction "1_1") (pintype "passive"))
      (node (ref "A2C1") (pin "1") (pinfunction "1_1") (pintype "passive"))
      (node (ref "A2C2") (pin "1") (pinfunction "1_1") (pintype "passive"))
      (node (ref "A3C1") (pin "1") (pinfunction "1_1") (pintype "passive"))
      (node (ref "A3C2") (pin "1") (pinfunction "1_1") (pintype "passive"))
      (node (ref "A4C1") (pin "1") (pinfunction "1_1") (pintype "passive"))
      (node (ref "A4C2") (pin "1") (pinfunction "1_1") (pintype "passive"))
      (node (ref "C1") (pin "1") (pinfunction "1_1") (pintype "passive"))
      (node (ref "C2") (pin "1") (pinfunction "1_1") (pintype "passive"))
      (node (ref "C3") (pin "1") (pinfunction "1_1") (pintype "passive"))
      (node (ref "C4") (pin "2") (pinfunction "2_2") (pintype "passive"))
      (node (ref "C5") (pin "2") (pinfunction "2_2") (pintype "passive"))
      (node (ref "C6") (pin "2") (pinfunction "2_2") (pintype "passive"))
      (node (ref "IC1") (pin "16") (pinfunction "VDD_IO_16") (pintype "power_in"))
      (node (ref "IC2") (pin "16") (pinfunction "VDD_IO_16") (pintype "power_in"))
      (node (ref "IC3") (pin "16") (pinfunction "VDD_IO_16") (pintype "power_in"))
      (node (ref "IC4") (pin "16") (pinfunction "VDD_IO_16") (pintype "power_in"))
      (node (ref "IC5") (pin "11") (pinfunction "VDD_2_11") (pintype "power_in"))
      (node (ref "IC5") (pin "15") (pinfunction "VDD_3_15") (pintype "power_in"))
      (node (ref "IC5") (pin "16") (pinfunction "VDD_4_16") (pintype "power_in"))
      (node (ref "IC5") (pin "20") (pinfunction "VDD_5_20") (pintype "power_in"))
      (node (ref "IC5") (pin "4") (pinfunction "VDD_1_4") (pintype "power_in"))
      (node (ref "JP1") (pin "12") (pinfunction "12_12") (pintype "passive"))
      (node (ref "JP1") (pin "16") (pinfunction "16_16") (pintype "passive"))
    )
    (net (code "10") (name "MCU_CLK") (class "Default")
      (node (ref "IC1") (pin "11") (pinfunction "CLK_11") (pintype "input"))
      (node (ref "IC2") (pin "11") (pinfunction "CLK_11") (pintype "input"))
      (node (ref "IC3") (pin "11") (pinfunction "CLK_11") (pintype "input"))
      (node (ref "IC4") (pin "11") (pinfunction "CLK_11") (pintype "input"))
      (node (ref "JP1") (pin "1") (pinfunction "1_1") (pintype "passive"))
    )
    (net (code "11") (name "MCU_IRQ_1") (class "Default")
      (node (ref "A1R1") (pin "1") (pinfunction "1_1") (pintype "passive"))
      (node (ref "JP1") (pin "36") (pinfunction "36_36") (pintype "passive"))
    )
    (net (code "12") (name "MCU_IRQ_2") (class "Default")
      (node (ref "A2R1") (pin "1") (pinfunction "1_1") (pintype "passive"))
      (node (ref "JP1") (pin "35") (pinfunction "35_35") (pintype "passive"))
    )
    (net (code "13") (name "MCU_IRQ_3") (class "Default")
      (node (ref "A3R1") (pin "1") (pinfunction "1_1") (pintype "passive"))
      (node (ref "JP1") (pin "38") (pinfunction "38_38") (pintype "passive"))
    )
    (net (code "14") (name "MCU_IRQ_4") (class "Default")
      (node (ref "A4R1") (pin "1") (pinfunction "1_1") (pintype "passive"))
      (node (ref "JP1") (pin "37") (pinfunction "37_37") (pintype "passive"))
    )
    (net (code "15") (name "MCU_MISO") (class "Default")
      (node (ref "A1R2") (pin "1") (pinfunction "1_1") (pintype "passive"))
      (node (ref "A2R2") (pin "1") (pinfunction "1_1") (pintype "passive"))
      (node (ref "A3R2") (pin "1") (pinfunction "1_1") (pintype "passive"))
      (node (ref "A4R2") (pin "1") (pinfunction "1_1") (pintype "passive"))
      (node (ref "JP1") (pin "2") (pinfunction "2_2") (pintype "passive"))
    )
    (net (code "16") (name "MCU_MOSI") (class "Default")
      (node (ref "IC1") (pin "13") (pinfunction "MOSI_13") (pintype "input"))
      (node (ref "IC2") (pin "13") (pinfunction "MOSI_13") (pintype "input"))
      (node (ref "IC3") (pin "13") (pinfunction "MOSI_13") (pintype "input"))
      (node (ref "IC4") (pin "13") (pinfunction "MOSI_13") (pintype "input"))
      (node (ref "JP1") (pin "3") (pinfunction "3_3") (pintype "passive"))
    )
    (net (code "17") (name "MCU_SEL1") (class "Default")
      (node (ref "IC1") (pin "10") (pinfunction "SEL_10") (pintype "input"))
      (node (ref "JP1") (pin "21") (pinfunction "21_21") (pintype "passive"))
    )
    (net (code "18") (name "MCU_SEL2") (class "Default")
      (node (ref "IC2") (pin "10") (pinfunction "SEL_10") (pintype "input"))
      (node (ref "JP1") (pin "28") (pinfunction "28_28") (pintype "passive"))
    )
    (net (code "19") (name "MCU_SEL3") (class "Default")
      (node (ref "IC3") (pin "10") (pinfunction "SEL_10") (pintype "input"))
      (node (ref "JP1") (pin "30") (pinfunction "30_30") (pintype "passive"))
    )
    (net (code "20") (name "MCU_SEL4") (class "Default")
      (node (ref "IC4") (pin "10") (pinfunction "SEL_10") (pintype "input"))
      (node (ref "JP1") (pin "34") (pinfunction "34_34") (pintype "passive"))
    )
    (net (code "21") (name "Net-(AX1_C1-Pad1)") (class "Default")
      (node (ref "AX1_C1") (pin "1") (pinfunction "1_1") (pintype "passive"))
      (node (ref "IC1") (pin "5") (pinfunction "VDD_ANA_5") (pintype "passive"))
    )
    (net (code "22") (name "Net-(AX1_C2-Pad1)") (class "Default")
      (node (ref "AX1_C2") (pin "1") (pinfunction "1_1") (pintype "passive"))
      (node (ref "IC1") (pin "1") (pinfunction "VDD_ANA_1") (pintype "passive"))
    )
    (net (code "23") (name "Net-(AX1_C3-Pad1)") (class "Default")
      (node (ref "AX1_C3") (pin "1") (pinfunction "1_1") (pintype "passive"))
      (node (ref "AX1_L4") (pin "2") (pinfunction "2_2") (pintype "passive"))
    )
    (net (code "24") (name "Net-(AX1_C4-Pad1)") (class "Default")
      (node (ref "AX1_C4") (pin "1") (pinfunction "1_1") (pintype "passive"))
      (node (ref "AX1_L5") (pin "2") (pinfunction "2_2") (pintype "passive"))
    )
    (net (code "25") (name "Net-(AX1_C5-Pad2)") (class "Default")
      (node (ref "AX1_C5") (pin "2") (pinfunction "2_2") (pintype "passive"))
      (node (ref "AX1_L4") (pin "1") (pinfunction "1_1") (pintype "passive"))
      (node (ref "AX1_L7") (pin "2") (pinfunction "2_2") (pintype "passive"))
    )
    (net (code "26") (name "Net-(AX1_C6-Pad2)") (class "Default")
      (node (ref "AX1_C6") (pin "2") (pinfunction "2_2") (pintype "passive"))
      (node (ref "AX1_C7") (pin "2") (pinfunction "2_2") (pintype "passive"))
      (node (ref "AX1_L5") (pin "1") (pinfunction "1_1") (pintype "passive"))
      (node (ref "AX1_L6") (pin "2") (pinfunction "2_2") (pintype "passive"))
    )
    (net (code "27") (name "Net-(AX1_C7-Pad1)") (class "Default")
      (node (ref "AX1_C7") (pin "1") (pinfunction "1_1") (pintype "passive"))
      (node (ref "AX1_C8") (pin "2") (pinfunction "2_2") (pintype "passive"))
      (node (ref "AX1_C9") (pin "1") (pinfunction "1_1") (pintype "passive"))
      (node (ref "AX1_L7") (pin "1") (pinfunction "1_1") (pintype "passive"))
      (node (ref "AX1_L8") (pin "2") (pinfunction "2_2") (pintype "passive"))
    )
    (net (code "28") (name "Net-(AX1_C10-Pad1)") (class "Default")
      (node (ref "AX1_C10") (pin "1") (pinfunction "1_1") (pintype "passive"))
      (node (ref "AX1_C8") (pin "1") (pinfunction "1_1") (pintype "passive"))
      (node (ref "AX1_L8") (pin "1") (pinfunction "1_1") (pintype "passive"))
      (node (ref "J1") (pin "1") (pinfunction "1_1") (pintype "passive"))
    )
    (net (code "29") (name "Net-(AX2_C1-Pad1)") (class "Default")
      (node (ref "AX2_C1") (pin "1") (pinfunction "1_1") (pintype "passive"))
      (node (ref "IC2") (pin "5") (pinfunction "VDD_ANA_5") (pintype "passive"))
    )
    (net (code "30") (name "Net-(AX2_C2-Pad1)") (class "Default")
      (node (ref "AX2_C2") (pin "1") (pinfunction "1_1") (pintype "passive"))
      (node (ref "IC2") (pin "1") (pinfunction "VDD_ANA_1") (pintype "passive"))
    )
    (net (code "31") (name "Net-(AX2_C3-Pad1)") (class "Default")
      (node (ref "AX2_C3") (pin "1") (pinfunction "1_1") (pintype "passive"))
      (node (ref "AX2_L4") (pin "2") (pinfunction "2_2") (pintype "passive"))
    )
    (net (code "32") (name "Net-(AX2_C4-Pad1)") (class "Default")
      (node (ref "AX2_C4") (pin "1") (pinfunction "1_1") (pintype "passive"))
      (node (ref "AX2_L5") (pin "2") (pinfunction "2_2") (pintype "passive"))
    )
    (net (code "33") (name "Net-(AX2_C5-Pad2)") (class "Default")
      (node (ref "AX2_C5") (pin "2") (pinfunction "2_2") (pintype "passive"))
      (node (ref "AX2_L4") (pin "1") (pinfunction "1_1") (pintype "passive"))
      (node (ref "AX2_L7") (pin "2") (pinfunction "2_2") (pintype "passive"))
    )
    (net (code "34") (name "Net-(AX2_C6-Pad2)") (class "Default")
      (node (ref "AX2_C6") (pin "2") (pinfunction "2_2") (pintype "passive"))
      (node (ref "AX2_C7") (pin "2") (pinfunction "2_2") (pintype "passive"))
      (node (ref "AX2_L5") (pin "1") (pinfunction "1_1") (pintype "passive"))
      (node (ref "AX2_L6") (pin "2") (pinfunction "2_2") (pintype "passive"))
    )
    (net (code "35") (name "Net-(AX2_C7-Pad1)") (class "Default")
      (node (ref "AX2_C7") (pin "1") (pinfunction "1_1") (pintype "passive"))
      (node (ref "AX2_C8") (pin "2") (pinfunction "2_2") (pintype "passive"))
      (node (ref "AX2_C9") (pin "1") (pinfunction "1_1") (pintype "passive"))
      (node (ref "AX2_L7") (pin "1") (pinfunction "1_1") (pintype "passive"))
      (node (ref "AX2_L8") (pin "2") (pinfunction "2_2") (pintype "passive"))
    )
    (net (code "36") (name "Net-(AX2_C10-Pad1)") (class "Default")
      (node (ref "AX2_C10") (pin "1") (pinfunction "1_1") (pintype "passive"))
      (node (ref "AX2_C8") (pin "1") (pinfunction "1_1") (pintype "passive"))
      (node (ref "AX2_L8") (pin "1") (pinfunction "1_1") (pintype "passive"))
      (node (ref "J2") (pin "1") (pinfunction "1_1") (pintype "passive"))
    )
    (net (code "37") (name "Net-(AX3_C1-Pad1)") (class "Default")
      (node (ref "AX3_C1") (pin "1") (pinfunction "1_1") (pintype "passive"))
      (node (ref "IC3") (pin "5") (pinfunction "VDD_ANA_5") (pintype "passive"))
    )
    (net (code "38") (name "Net-(AX3_C2-Pad1)") (class "Default")
      (node (ref "AX3_C2") (pin "1") (pinfunction "1_1") (pintype "passive"))
      (node (ref "IC3") (pin "1") (pinfunction "VDD_ANA_1") (pintype "passive"))
    )
    (net (code "39") (name "Net-(AX3_C3-Pad1)") (class "Default")
      (node (ref "AX3_C3") (pin "1") (pinfunction "1_1") (pintype "passive"))
      (node (ref "AX3_L4") (pin "2") (pinfunction "2_2") (pintype "passive"))
    )
    (net (code "40") (name "Net-(AX3_C4-Pad1)") (class "Default")
      (node (ref "AX3_C4") (pin "1") (pinfunction "1_1") (pintype "passive"))
      (node (ref "AX3_L5") (pin "2") (pinfunction "2_2") (pintype "passive"))
    )
    (net (code "41") (name "Net-(AX3_C5-Pad2)") (class "Default")
      (node (ref "AX3_C5") (pin "2") (pinfunction "2_2") (pintype "passive"))
      (node (ref "AX3_L4") (pin "1") (pinfunction "1_1") (pintype "passive"))
      (node (ref "AX3_L7") (pin "2") (pinfunction "2_2") (pintype "passive"))
    )
    (net (code "42") (name "Net-(AX3_C6-Pad2)") (class "Default")
      (node (ref "AX3_C6") (pin "2") (pinfunction "2_2") (pintype "passive"))
      (node (ref "AX3_C7") (pin "2") (pinfunction "2_2") (pintype "passive"))
      (node (ref "AX3_L5") (pin "1") (pinfunction "1_1") (pintype "passive"))
      (node (ref "AX3_L6") (pin "2") (pinfunction "2_2") (pintype "passive"))
    )
    (net (code "43") (name "Net-(AX3_C7-Pad1)") (class "Default")
      (node (ref "AX3_C7") (pin "1") (pinfunction "1_1") (pintype "passive"))
      (node (ref "AX3_C8") (pin "2") (pinfunction "2_2") (pintype "passive"))
      (node (ref "AX3_C9") (pin "1") (pinfunction "1_1") (pintype "passive"))
      (node (ref "AX3_L7") (pin "1") (pinfunction "1_1") (pintype "passive"))
      (node (ref "AX3_L8") (pin "2") (pinfunction "2_2") (pintype "passive"))
    )
    (net (code "44") (name "Net-(AX3_C10-Pad1)") (class "Default")
      (node (ref "AX3_C10") (pin "1") (pinfunction "1_1") (pintype "passive"))
      (node (ref "AX3_C8") (pin "1") (pinfunction "1_1") (pintype "passive"))
      (node (ref "AX3_L8") (pin "1") (pinfunction "1_1") (pintype "passive"))
      (node (ref "J3") (pin "1") (pinfunction "1_1") (pintype "passive"))
    )
    (net (code "45") (name "Net-(AX4_C1-Pad1)") (class "Default")
      (node (ref "AX4_C1") (pin "1") (pinfunction "1_1") (pintype "passive"))
      (node (ref "IC4") (pin "5") (pinfunction "VDD_ANA_5") (pintype "passive"))
    )
    (net (code "46") (name "Net-(AX4_C2-Pad1)") (class "Default")
      (node (ref "AX4_C2") (pin "1") (pinfunction "1_1") (pintype "passive"))
      (node (ref "IC4") (pin "1") (pinfunction "VDD_ANA_1") (pintype "passive"))
    )
    (net (code "47") (name "Net-(AX4_C3-Pad1)") (class "Default")
      (node (ref "AX4_C3") (pin "1") (pinfunction "1_1") (pintype "passive"))
      (node (ref "AX4_L4") (pin "2") (pinfunction "2_2") (pintype "passive"))
    )
    (net (code "48") (name "Net-(AX4_C4-Pad1)") (class "Default")
      (node (ref "AX4_C4") (pin "1") (pinfunction "1_1") (pintype "passive"))
      (node (ref "AX4_L5") (pin "2") (pinfunction "2_2") (pintype "passive"))
    )
    (net (code "49") (name "Net-(AX4_C5-Pad2)") (class "Default")
      (node (ref "AX4_C5") (pin "2") (pinfunction "2_2") (pintype "passive"))
      (node (ref "AX4_L4") (pin "1") (pinfunction "1_1") (pintype "passive"))
      (node (ref "AX4_L7") (pin "2") (pinfunction "2_2") (pintype "passive"))
    )
    (net (code "50") (name "Net-(AX4_C6-Pad2)") (class "Default")
      (node (ref "AX4_C6") (pin "2") (pinfunction "2_2") (pintype "passive"))
      (node (ref "AX4_C7") (pin "2") (pinfunction "2_2") (pintype "passive"))
      (node (ref "AX4_L5") (pin "1") (pinfunction "1_1") (pintype "passive"))
      (node (ref "AX4_L6") (pin "2") (pinfunction "2_2") (pintype "passive"))
    )
    (net (code "51") (name "Net-(AX4_C7-Pad1)") (class "Default")
      (node (ref "AX4_C7") (pin "1") (pinfunction "1_1") (pintype "passive"))
      (node (ref "AX4_C8") (pin "2") (pinfunction "2_2") (pintype "passive"))
      (node (ref "AX4_C9") (pin "1") (pinfunction "1_1") (pintype "passive"))
      (node (ref "AX4_L7") (pin "1") (pinfunction "1_1") (pintype "passive"))
      (node (ref "AX4_L8") (pin "2") (pinfunction "2_2") (pintype "passive"))
    )
    (net (code "52") (name "Net-(AX4_C10-Pad1)") (class "Default")
      (node (ref "AX4_C10") (pin "1") (pinfunction "1_1") (pintype "passive"))
      (node (ref "AX4_C8") (pin "1") (pinfunction "1_1") (pintype "passive"))
      (node (ref "AX4_L8") (pin "1") (pinfunction "1_1") (pintype "passive"))
      (node (ref "J4") (pin "1") (pinfunction "1_1") (pintype "passive"))
    )
    (net (code "53") (name "Net-(CT1-E)") (class "Default")
      (node (ref "CT1") (pin "-") (pinfunction "E_-") (pintype "passive"))
      (node (ref "IC5") (pin "3") (pinfunction "X1_3") (pintype "passive"))
      (node (ref "Q2") (pin "1") (pinfunction "1_1") (pintype "passive"))
    )
    (net (code "54") (name "Net-(IC1-ANTN)") (class "Default")
      (node (ref "AX1_C4") (pin "2") (pinfunction "2_2") (pintype "passive"))
      (node (ref "AX1_L2") (pin "2") (pinfunction "2_2") (pintype "passive"))
      (node (ref "IC1") (pin "4") (pinfunction "ANTN_4") (pintype "passive"))
    )
    (net (code "55") (name "Net-(IC1-ANTP)") (class "Default")
      (node (ref "AX1_C3") (pin "2") (pinfunction "2_2") (pintype "passive"))
      (node (ref "AX1_L3") (pin "1") (pinfunction "1_1") (pintype "passive"))
      (node (ref "IC1") (pin "3") (pinfunction "ANTP_3") (pintype "passive"))
    )
    (net (code "56") (name "Net-(IC1-CLK16P)") (class "Default")
      (node (ref "AX1_C13") (pin "1") (pinfunction "1_1") (pintype "passive"))
      (node (ref "AX1_C14") (pin "1") (pinfunction "1_1") (pintype "passive"))
      (node (ref "IC1") (pin "20") (pinfunction "CLK16P_20") (pintype "passive"))
    )
    (net (code "57") (name "Net-(IC1-IRQ)") (class "Default")
      (node (ref "A1R1") (pin "2") (pinfunction "2_2") (pintype "passive"))
      (node (ref "IC1") (pin "14") (pinfunction "IRQ_14") (pintype "bidirectional"))
    )
    (net (code "58") (name "Net-(IC1-L1)") (class "Default")
      (node (ref "AX1_L1") (pin "2") (pinfunction "2_2") (pintype "passive"))
      (node (ref "IC1") (pin "8") (pinfunction "L1_8") (pintype "passive"))
    )
    (net (code "59") (name "Net-(IC1-L2)") (class "Default")
      (node (ref "AX1_L1") (pin "1") (pinfunction "1_1") (pintype "passive"))
      (node (ref "IC1") (pin "7") (pinfunction "L2_7") (pintype "passive"))
    )
    (net (code "60") (name "Net-(IC1-MISO)") (class "Default")
      (node (ref "A1R2") (pin "2") (pinfunction "2_2") (pintype "passive"))
      (node (ref "IC1") (pin "12") (pinfunction "MISO_12") (pintype "output"))
    )
    (net (code "61") (name "Net-(IC2-ANTN)") (class "Default")
      (node (ref "AX2_C4") (pin "2") (pinfunction "2_2") (pintype "passive"))
      (node (ref "AX2_L2") (pin "2") (pinfunction "2_2") (pintype "passive"))
      (node (ref "IC2") (pin "4") (pinfunction "ANTN_4") (pintype "passive"))
    )
    (net (code "62") (name "Net-(IC2-ANTP)") (class "Default")
      (node (ref "AX2_C3") (pin "2") (pinfunction "2_2") (pintype "passive"))
      (node (ref "AX2_L3") (pin "1") (pinfunction "1_1") (pintype "passive"))
      (node (ref "IC2") (pin "3") (pinfunction "ANTP_3") (pintype "passive"))
    )
    (net (code "63") (name "Net-(IC2-CLK16P)") (class "Default")
      (node (ref "AX2_C13") (pin "1") (pinfunction "1_1") (pintype "passive"))
      (node (ref "AX2_C14") (pin "1") (pinfunction "1_1") (pintype "passive"))
      (node (ref "IC2") (pin "20") (pinfunction "CLK16P_20") (pintype "passive"))
    )
    (net (code "64") (name "Net-(IC2-IRQ)") (class "Default")
      (node (ref "A2R1") (pin "2") (pinfunction "2_2") (pintype "passive"))
      (node (ref "IC2") (pin "14") (pinfunction "IRQ_14") (pintype "bidirectional"))
    )
    (net (code "65") (name "Net-(IC2-L1)") (class "Default")
      (node (ref "AX2_L1") (pin "2") (pinfunction "2_2") (pintype "passive"))
      (node (ref "IC2") (pin "8") (pinfunction "L1_8") (pintype "passive"))
    )
    (net (code "66") (name "Net-(IC2-L2)") (class "Default")
      (node (ref "AX2_L1") (pin "1") (pinfunction "1_1") (pintype "passive"))
      (node (ref "IC2") (pin "7") (pinfunction "L2_7") (pintype "passive"))
    )
    (net (code "67") (name "Net-(IC2-MISO)") (class "Default")
      (node (ref "A2R2") (pin "2") (pinfunction "2_2") (pintype "passive"))
      (node (ref "IC2") (pin "12") (pinfunction "MISO_12") (pintype "output"))
    )
    (net (code "68") (name "Net-(IC3-ANTN)") (class "Default")
      (node (ref "AX3_C4") (pin "2") (pinfunction "2_2") (pintype "passive"))
      (node (ref "AX3_L2") (pin "2") (pinfunction "2_2") (pintype "passive"))
      (node (ref "IC3") (pin "4") (pinfunction "ANTN_4") (pintype "passive"))
    )
    (net (code "69") (name "Net-(IC3-ANTP)") (class "Default")
      (node (ref "AX3_C3") (pin "2") (pinfunction "2_2") (pintype "passive"))
      (node (ref "AX3_L3") (pin "1") (pinfunction "1_1") (pintype "passive"))
      (node (ref "IC3") (pin "3") (pinfunction "ANTP_3") (pintype "passive"))
    )
    (net (code "70") (name "Net-(IC3-CLK16P)") (class "Default")
      (node (ref "AX3_C13") (pin "1") (pinfunction "1_1") (pintype "passive"))
      (node (ref "AX3_C14") (pin "1") (pinfunction "1_1") (pintype "passive"))
      (node (ref "IC3") (pin "20") (pinfunction "CLK16P_20") (pintype "passive"))
    )
    (net (code "71") (name "Net-(IC3-IRQ)") (class "Default")
      (node (ref "A3R1") (pin "2") (pinfunction "2_2") (pintype "passive"))
      (node (ref "IC3") (pin "14") (pinfunction "IRQ_14") (pintype "bidirectional"))
    )
    (net (code "72") (name "Net-(IC3-L1)") (class "Default")
      (node (ref "AX3_L1") (pin "2") (pinfunction "2_2") (pintype "passive"))
      (node (ref "IC3") (pin "8") (pinfunction "L1_8") (pintype "passive"))
    )
    (net (code "73") (name "Net-(IC3-L2)") (class "Default")
      (node (ref "AX3_L1") (pin "1") (pinfunction "1_1") (pintype "passive"))
      (node (ref "IC3") (pin "7") (pinfunction "L2_7") (pintype "passive"))
    )
    (net (code "74") (name "Net-(IC3-MISO)") (class "Default")
      (node (ref "A3R2") (pin "2") (pinfunction "2_2") (pintype "passive"))
      (node (ref "IC3") (pin "12") (pinfunction "MISO_12") (pintype "output"))
    )
    (net (code "75") (name "Net-(IC4-ANTN)") (class "Default")
      (node (ref "AX4_C4") (pin "2") (pinfunction "2_2") (pintype "passive"))
      (node (ref "AX4_L2") (pin "2") (pinfunction "2_2") (pintype "passive"))
      (node (ref "IC4") (pin "4") (pinfunction "ANTN_4") (pintype "passive"))
    )
    (net (code "76") (name "Net-(IC4-ANTP)") (class "Default")
      (node (ref "AX4_C3") (pin "2") (pinfunction "2_2") (pintype "passive"))
      (node (ref "AX4_L3") (pin "1") (pinfunction "1_1") (pintype "passive"))
      (node (ref "IC4") (pin "3") (pinfunction "ANTP_3") (pintype "passive"))
    )
    (net (code "77") (name "Net-(IC4-CLK16P)") (class "Default")
      (node (ref "AX4_C13") (pin "1") (pinfunction "1_1") (pintype "passive"))
      (node (ref "AX4_C14") (pin "1") (pinfunction "1_1") (pintype "passive"))
      (node (ref "IC4") (pin "20") (pinfunction "CLK16P_20") (pintype "passive"))
    )
    (net (code "78") (name "Net-(IC4-IRQ)") (class "Default")
      (node (ref "A4R1") (pin "2") (pinfunction "2_2") (pintype "passive"))
      (node (ref "IC4") (pin "14") (pinfunction "IRQ_14") (pintype "bidirectional"))
    )
    (net (code "79") (name "Net-(IC4-L1)") (class "Default")
      (node (ref "AX4_L1") (pin "2") (pinfunction "2_2") (pintype "passive"))
      (node (ref "IC4") (pin "8") (pinfunction "L1_8") (pintype "passive"))
    )
    (net (code "80") (name "Net-(IC4-L2)") (class "Default")
      (node (ref "AX4_L1") (pin "1") (pinfunction "1_1") (pintype "passive"))
      (node (ref "IC4") (pin "7") (pinfunction "L2_7") (pintype "passive"))
    )
    (net (code "81") (name "Net-(IC4-MISO)") (class "Default")
      (node (ref "A4R2") (pin "2") (pinfunction "2_2") (pintype "passive"))
      (node (ref "IC4") (pin "12") (pinfunction "MISO_12") (pintype "output"))
    )
    (net (code "82") (name "Net-(IC5-CLK_1)") (class "Default")
      (node (ref "IC5") (pin "7") (pinfunction "CLK_1_7") (pintype "tri_state"))
      (node (ref "R1") (pin "1") (pinfunction "1_1") (pintype "passive"))
    )
    (net (code "83") (name "Net-(IC5-CLK_2)") (class "Default")
      (node (ref "IC5") (pin "8") (pinfunction "CLK_2_8") (pintype "tri_state"))
      (node (ref "R2") (pin "1") (pinfunction "1_1") (pintype "passive"))
    )
    (net (code "84") (name "Net-(IC5-CLK_3)") (class "Default")
      (node (ref "IC5") (pin "9") (pinfunction "CLK_3_9") (pintype "tri_state"))
      (node (ref "R3") (pin "1") (pinfunction "1_1") (pintype "passive"))
    )
    (net (code "85") (name "Net-(IC5-CLK_4)") (class "Default")
      (node (ref "IC5") (pin "10") (pinfunction "CLK_4_10") (pintype "tri_state"))
      (node (ref "R4") (pin "1") (pinfunction "1_1") (pintype "passive"))
    )
    (net (code "86") (name "Net-(IC5-CLK_5)") (class "Default")
      (node (ref "IC5") (pin "12") (pinfunction "CLK_5_12") (pintype "tri_state"))
      (node (ref "R5") (pin "1") (pinfunction "1_1") (pintype "passive"))
    )
    (net (code "87") (name "Net-(IC5-X2)") (class "Default")
      (node (ref "C7") (pin "1") (pinfunction "1_1") (pintype "passive"))
      (node (ref "IC5") (pin "2") (pinfunction "X2_2") (pintype "passive"))
      (node (ref "Q2") (pin "3") (pinfunction "2_3") (pintype "passive"))
    )
    (net (code "88") (name "VDD") (class "Default")
      (node (ref "JP1") (pin "5") (pinfunction "5_5") (pintype "passive"))
    )
    (net (code "89") (name "unconnected-(IC1-CLK16N-Pad19)") (class "Default")
      (node (ref "IC1") (pin "19") (pinfunction "CLK16N_19") (pintype "passive"))
    )
    (net (code "90") (name "unconnected-(IC1-FILT-Pad6)") (class "Default")
      (node (ref "IC1") (pin "6") (pinfunction "FILT_6") (pintype "passive"))
    )
    (net (code "91") (name "unconnected-(IC1-SYSCLK-Pad9)") (class "Default")
      (node (ref "IC1") (pin "9") (pinfunction "SYSCLK_9") (pintype "bidirectional"))
    )
    (net (code "92") (name "unconnected-(IC1-TCXO_EN-Pad15)") (class "Default")
      (node (ref "IC1") (pin "15") (pinfunction "TCXO_EN_15") (pintype "bidirectional"))
    )
    (net (code "93") (name "unconnected-(IC2-CLK16N-Pad19)") (class "Default")
      (node (ref "IC2") (pin "19") (pinfunction "CLK16N_19") (pintype "passive"))
    )
    (net (code "94") (name "unconnected-(IC2-FILT-Pad6)") (class "Default")
      (node (ref "IC2") (pin "6") (pinfunction "FILT_6") (pintype "passive"))
    )
    (net (code "95") (name "unconnected-(IC2-SYSCLK-Pad9)") (class "Default")
      (node (ref "IC2") (pin "9") (pinfunction "SYSCLK_9") (pintype "bidirectional"))
    )
    (net (code "96") (name "unconnected-(IC2-TCXO_EN-Pad15)") (class "Default")
      (node (ref "IC2") (pin "15") (pinfunction "TCXO_EN_15") (pintype "bidirectional"))
    )
    (net (code "97") (name "unconnected-(IC3-CLK16N-Pad19)") (class "Default")
      (node (ref "IC3") (pin "19") (pinfunction "CLK16N_19") (pintype "passive"))
    )
    (net (code "98") (name "unconnected-(IC3-FILT-Pad6)") (class "Default")
      (node (ref "IC3") (pin "6") (pinfunction "FILT_6") (pintype "passive"))
    )
    (net (code "99") (name "unconnected-(IC3-SYSCLK-Pad9)") (class "Default")
      (node (ref "IC3") (pin "9") (pinfunction "SYSCLK_9") (pintype "bidirectional"))
    )
    (net (code "100") (name "unconnected-(IC3-TCXO_EN-Pad15)") (class "Default")
      (node (ref "IC3") (pin "15") (pinfunction "TCXO_EN_15") (pintype "bidirectional"))
    )
    (net (code "101") (name "unconnected-(IC4-CLK16N-Pad19)") (class "Default")
      (node (ref "IC4") (pin "19") (pinfunction "CLK16N_19") (pintype "passive"))
    )
    (net (code "102") (name "unconnected-(IC4-FILT-Pad6)") (class "Default")
      (node (ref "IC4") (pin "6") (pinfunction "FILT_6") (pintype "passive"))
    )
    (net (code "103") (name "unconnected-(IC4-SYSCLK-Pad9)") (class "Default")
      (node (ref "IC4") (pin "9") (pinfunction "SYSCLK_9") (pintype "bidirectional"))
    )
    (net (code "104") (name "unconnected-(IC4-TCXO_EN-Pad15)") (class "Default")
      (node (ref "IC4") (pin "15") (pinfunction "TCXO_EN_15") (pintype "bidirectional"))
    )
    (net (code "105") (name "unconnected-(IC5-CLK_6-Pad13)") (class "Default")
      (node (ref "IC5") (pin "13") (pinfunction "CLK_6_13") (pintype "tri_state"))
    )
    (net (code "106") (name "unconnected-(IC5-CLK_7-Pad17)") (class "Default")
      (node (ref "IC5") (pin "17") (pinfunction "CLK_7_17") (pintype "tri_state"))
    )
    (net (code "107") (name "unconnected-(IC5-CLK_8-Pad18)") (class "Default")
      (node (ref "IC5") (pin "18") (pinfunction "CLK_8_18") (pintype "tri_state"))
    )
    (net (code "108") (name "unconnected-(IC5-DC_1-Pad1)") (class "Default")
      (node (ref "IC5") (pin "1") (pinfunction "DC_1_1") (pintype "no_connect"))
    )
    (net (code "109") (name "unconnected-(IC5-DC_2-Pad19)") (class "Default")
      (node (ref "IC5") (pin "19") (pinfunction "DC_2_19") (pintype "no_connect"))
    )
    (net (code "110") (name "unconnected-(JP1-Pad4)") (class "Default")
      (node (ref "JP1") (pin "4") (pinfunction "4_4") (pintype "passive"))
    )
    (net (code "111") (name "unconnected-(JP1-Pad6)") (class "Default")
      (node (ref "JP1") (pin "6") (pinfunction "6_6") (pintype "passive"))
    )
    (net (code "112") (name "unconnected-(JP1-Pad7)") (class "Default")
      (node (ref "JP1") (pin "7") (pinfunction "7_7") (pintype "passive"))
    )
    (net (code "113") (name "unconnected-(JP1-Pad9)") (class "Default")
      (node (ref "JP1") (pin "9") (pinfunction "9_9") (pintype "passive"))
    )
    (net (code "114") (name "unconnected-(JP1-Pad10)") (class "Default")
      (node (ref "JP1") (pin "10") (pinfunction "10_10") (pintype "passive"))
    )
    (net (code "115") (name "unconnected-(JP1-Pad11)") (class "Default")
      (node (ref "JP1") (pin "11") (pinfunction "11_11") (pintype "passive"))
    )
    (net (code "116") (name "unconnected-(JP1-Pad13)") (class "Default")
      (node (ref "JP1") (pin "13") (pinfunction "13_13") (pintype "passive"))
    )
    (net (code "117") (name "unconnected-(JP1-Pad14)") (class "Default")
      (node (ref "JP1") (pin "14") (pinfunction "14_14") (pintype "passive"))
    )
    (net (code "118") (name "unconnected-(JP1-Pad15)") (class "Default")
      (node (ref "JP1") (pin "15") (pinfunction "15_15") (pintype "passive"))
    )
    (net (code "119") (name "unconnected-(JP1-Pad17)") (class "Default")
      (node (ref "JP1") (pin "17") (pinfunction "17_17") (pintype "passive"))
    )
    (net (code "120") (name "unconnected-(JP1-Pad18)") (class "Default")
      (node (ref "JP1") (pin "18") (pinfunction "18_18") (pintype "passive"))
    )
    (net (code "121") (name "unconnected-(JP1-Pad23)") (class "Default")
      (node (ref "JP1") (pin "23") (pinfunction "23_23") (pintype "passive"))
    )
    (net (code "122") (name "unconnected-(JP1-Pad24)") (class "Default")
      (node (ref "JP1") (pin "24") (pinfunction "24_24") (pintype "passive"))
    )
    (net (code "123") (name "unconnected-(JP1-Pad25)") (class "Default")
      (node (ref "JP1") (pin "25") (pinfunction "25_25") (pintype "passive"))
    )
    (net (code "124") (name "unconnected-(JP1-Pad26)") (class "Default")
      (node (ref "JP1") (pin "26") (pinfunction "26_26") (pintype "passive"))
    )
    (net (code "125") (name "unconnected-(JP1-Pad27)") (class "Default")
      (node (ref "JP1") (pin "27") (pinfunction "27_27") (pintype "passive"))
    )
    (net (code "126") (name "unconnected-(JP1-Pad31)") (class "Default")
      (node (ref "JP1") (pin "31") (pinfunction "31_31") (pintype "passive"))
    )
    (net (code "127") (name "unconnected-(JP1-Pad32)") (class "Default")
      (node (ref "JP1") (pin "32") (pinfunction "32_32") (pintype "passive"))
    )
    (net (code "128") (name "unconnected-(JP1-Pad33)") (class "Default")
      (node (ref "JP1") (pin "33") (pinfunction "33_33") (pintype "passive"))
    )
    (net (code "129") (name "unconnected-(JP2-Pad1)") (class "Default")
      (node (ref "JP2") (pin "1") (pinfunction "1_1") (pintype "passive"))
    )
    (net (code "130") (name "unconnected-(JP2-Pad2)") (class "Default")
      (node (ref "JP2") (pin "2") (pinfunction "2_2") (pintype "passive"))
    )
    (net (code "131") (name "unconnected-(JP2-Pad3)") (class "Default")
      (node (ref "JP2") (pin "3") (pinfunction "3_3") (pintype "passive"))
    )
    (net (code "132") (name "unconnected-(JP2-Pad4)") (class "Default")
      (node (ref "JP2") (pin "4") (pinfunction "4_4") (pintype "passive"))
    )
    (net (code "133") (name "unconnected-(JP2-Pad5)") (class "Default")
      (node (ref "JP2") (pin "5") (pinfunction "5_5") (pintype "passive"))
    )
    (net (code "134") (name "unconnected-(JP2-Pad6)") (class "Default")
      (node (ref "JP2") (pin "6") (pinfunction "6_6") (pintype "passive"))
    )
    (net (code "135") (name "unconnected-(JP2-Pad8)") (class "Default")
      (node (ref "JP2") (pin "8") (pinfunction "8_8") (pintype "passive"))
    )
    (net (code "136") (name "unconnected-(JP2-Pad10)") (class "Default")
      (node (ref "JP2") (pin "10") (pinfunction "10_10") (pintype "passive"))
    )
    (net (code "137") (name "unconnected-(JP2-Pad11)") (class "Default")
      (node (ref "JP2") (pin "11") (pinfunction "11_11") (pintype "passive"))
    )
    (net (code "138") (name "unconnected-(JP2-Pad12)") (class "Default")
      (node (ref "JP2") (pin "12") (pinfunction "12_12") (pintype "passive"))
    )
    (net (code "139") (name "unconnected-(JP2-Pad13)") (class "Default")
      (node (ref "JP2") (pin "13") (pinfunction "13_13") (pintype "passive"))
    )
    (net (code "140") (name "unconnected-(JP2-Pad14)") (class "Default")
      (node (ref "JP2") (pin "14") (pinfunction "14_14") (pintype "passive"))
    )
    (net (code "141") (name "unconnected-(JP2-Pad15)") (class "Default")
      (node (ref "JP2") (pin "15") (pinfunction "15_15") (pintype "passive"))
    )
    (net (code "142") (name "unconnected-(JP2-Pad16)") (class "Default")
      (node (ref "JP2") (pin "16") (pinfunction "16_16") (pintype "passive"))
    )
    (net (code "143") (name "unconnected-(JP2-Pad17)") (class "Default")
      (node (ref "JP2") (pin "17") (pinfunction "17_17") (pintype "passive"))
    )
    (net (code "144") (name "unconnected-(JP2-Pad18)") (class "Default")
      (node (ref "JP2") (pin "18") (pinfunction "18_18") (pintype "passive"))
    )
    (net (code "145") (name "unconnected-(JP2-Pad19)") (class "Default")
      (node (ref "JP2") (pin "19") (pinfunction "19_19") (pintype "passive"))
    )
    (net (code "146") (name "unconnected-(JP2-Pad21)") (class "Default")
      (node (ref "JP2") (pin "21") (pinfunction "21_21") (pintype "passive"))
    )
    (net (code "147") (name "unconnected-(JP2-Pad22)") (class "Default")
      (node (ref "JP2") (pin "22") (pinfunction "22_22") (pintype "passive"))
    )
    (net (code "148") (name "unconnected-(JP2-Pad23)") (class "Default")
      (node (ref "JP2") (pin "23") (pinfunction "23_23") (pintype "passive"))
    )
    (net (code "149") (name "unconnected-(JP2-Pad24)") (class "Default")
      (node (ref "JP2") (pin "24") (pinfunction "24_24") (pintype "passive"))
    )
    (net (code "150") (name "unconnected-(JP2-Pad25)") (class "Default")
      (node (ref "JP2") (pin "25") (pinfunction "25_25") (pintype "passive"))
    )
    (net (code "151") (name "unconnected-(JP2-Pad26)") (class "Default")
      (node (ref "JP2") (pin "26") (pinfunction "26_26") (pintype "passive"))
    )
    (net (code "152") (name "unconnected-(JP2-Pad27)") (class "Default")
      (node (ref "JP2") (pin "27") (pinfunction "27_27") (pintype "passive"))
    )
    (net (code "153") (name "unconnected-(JP2-Pad28)") (class "Default")
      (node (ref "JP2") (pin "28") (pinfunction "28_28") (pintype "passive"))
    )
    (net (code "154") (name "unconnected-(JP2-Pad29)") (class "Default")
      (node (ref "JP2") (pin "29") (pinfunction "29_29") (pintype "passive"))
    )
    (net (code "155") (name "unconnected-(JP2-Pad30)") (class "Default")
      (node (ref "JP2") (pin "30") (pinfunction "30_30") (pintype "passive"))
    )
    (net (code "156") (name "unconnected-(JP2-Pad31)") (class "Default")
      (node (ref "JP2") (pin "31") (pinfunction "31_31") (pintype "passive"))
    )
    (net (code "157") (name "unconnected-(JP2-Pad33)") (class "Default")
      (node (ref "JP2") (pin "33") (pinfunction "33_33") (pintype "passive"))
    )
    (net (code "158") (name "unconnected-(JP2-Pad34)") (class "Default")
      (node (ref "JP2") (pin "34") (pinfunction "34_34") (pintype "passive"))
    )
    (net (code "159") (name "unconnected-(JP2-Pad35)") (class "Default")
      (node (ref "JP2") (pin "35") (pinfunction "35_35") (pintype "passive"))
    )
    (net (code "160") (name "unconnected-(JP2-Pad36)") (class "Default")
      (node (ref "JP2") (pin "36") (pinfunction "36_36") (pintype "passive"))
    )
    (net (code "161") (name "unconnected-(JP2-Pad37)") (class "Default")
      (node (ref "JP2") (pin "37") (pinfunction "37_37") (pintype "passive"))
    )
    (net (code "162") (name "unconnected-(JP2-Pad38)") (class "Default")
      (node (ref "JP2") (pin "38") (pinfunction "38_38") (pintype "passive"))
    )
    (net (code "163") (name "unconnected-(TP1-PadTP)") (class "Default")
      (node (ref "TP1") (pin "TP") (pinfunction "TP_TP") (pintype "input"))
    )
  )
)
